# octanis_eps_v06.net
KiCad netlist of a schematic drawn in EAGLE
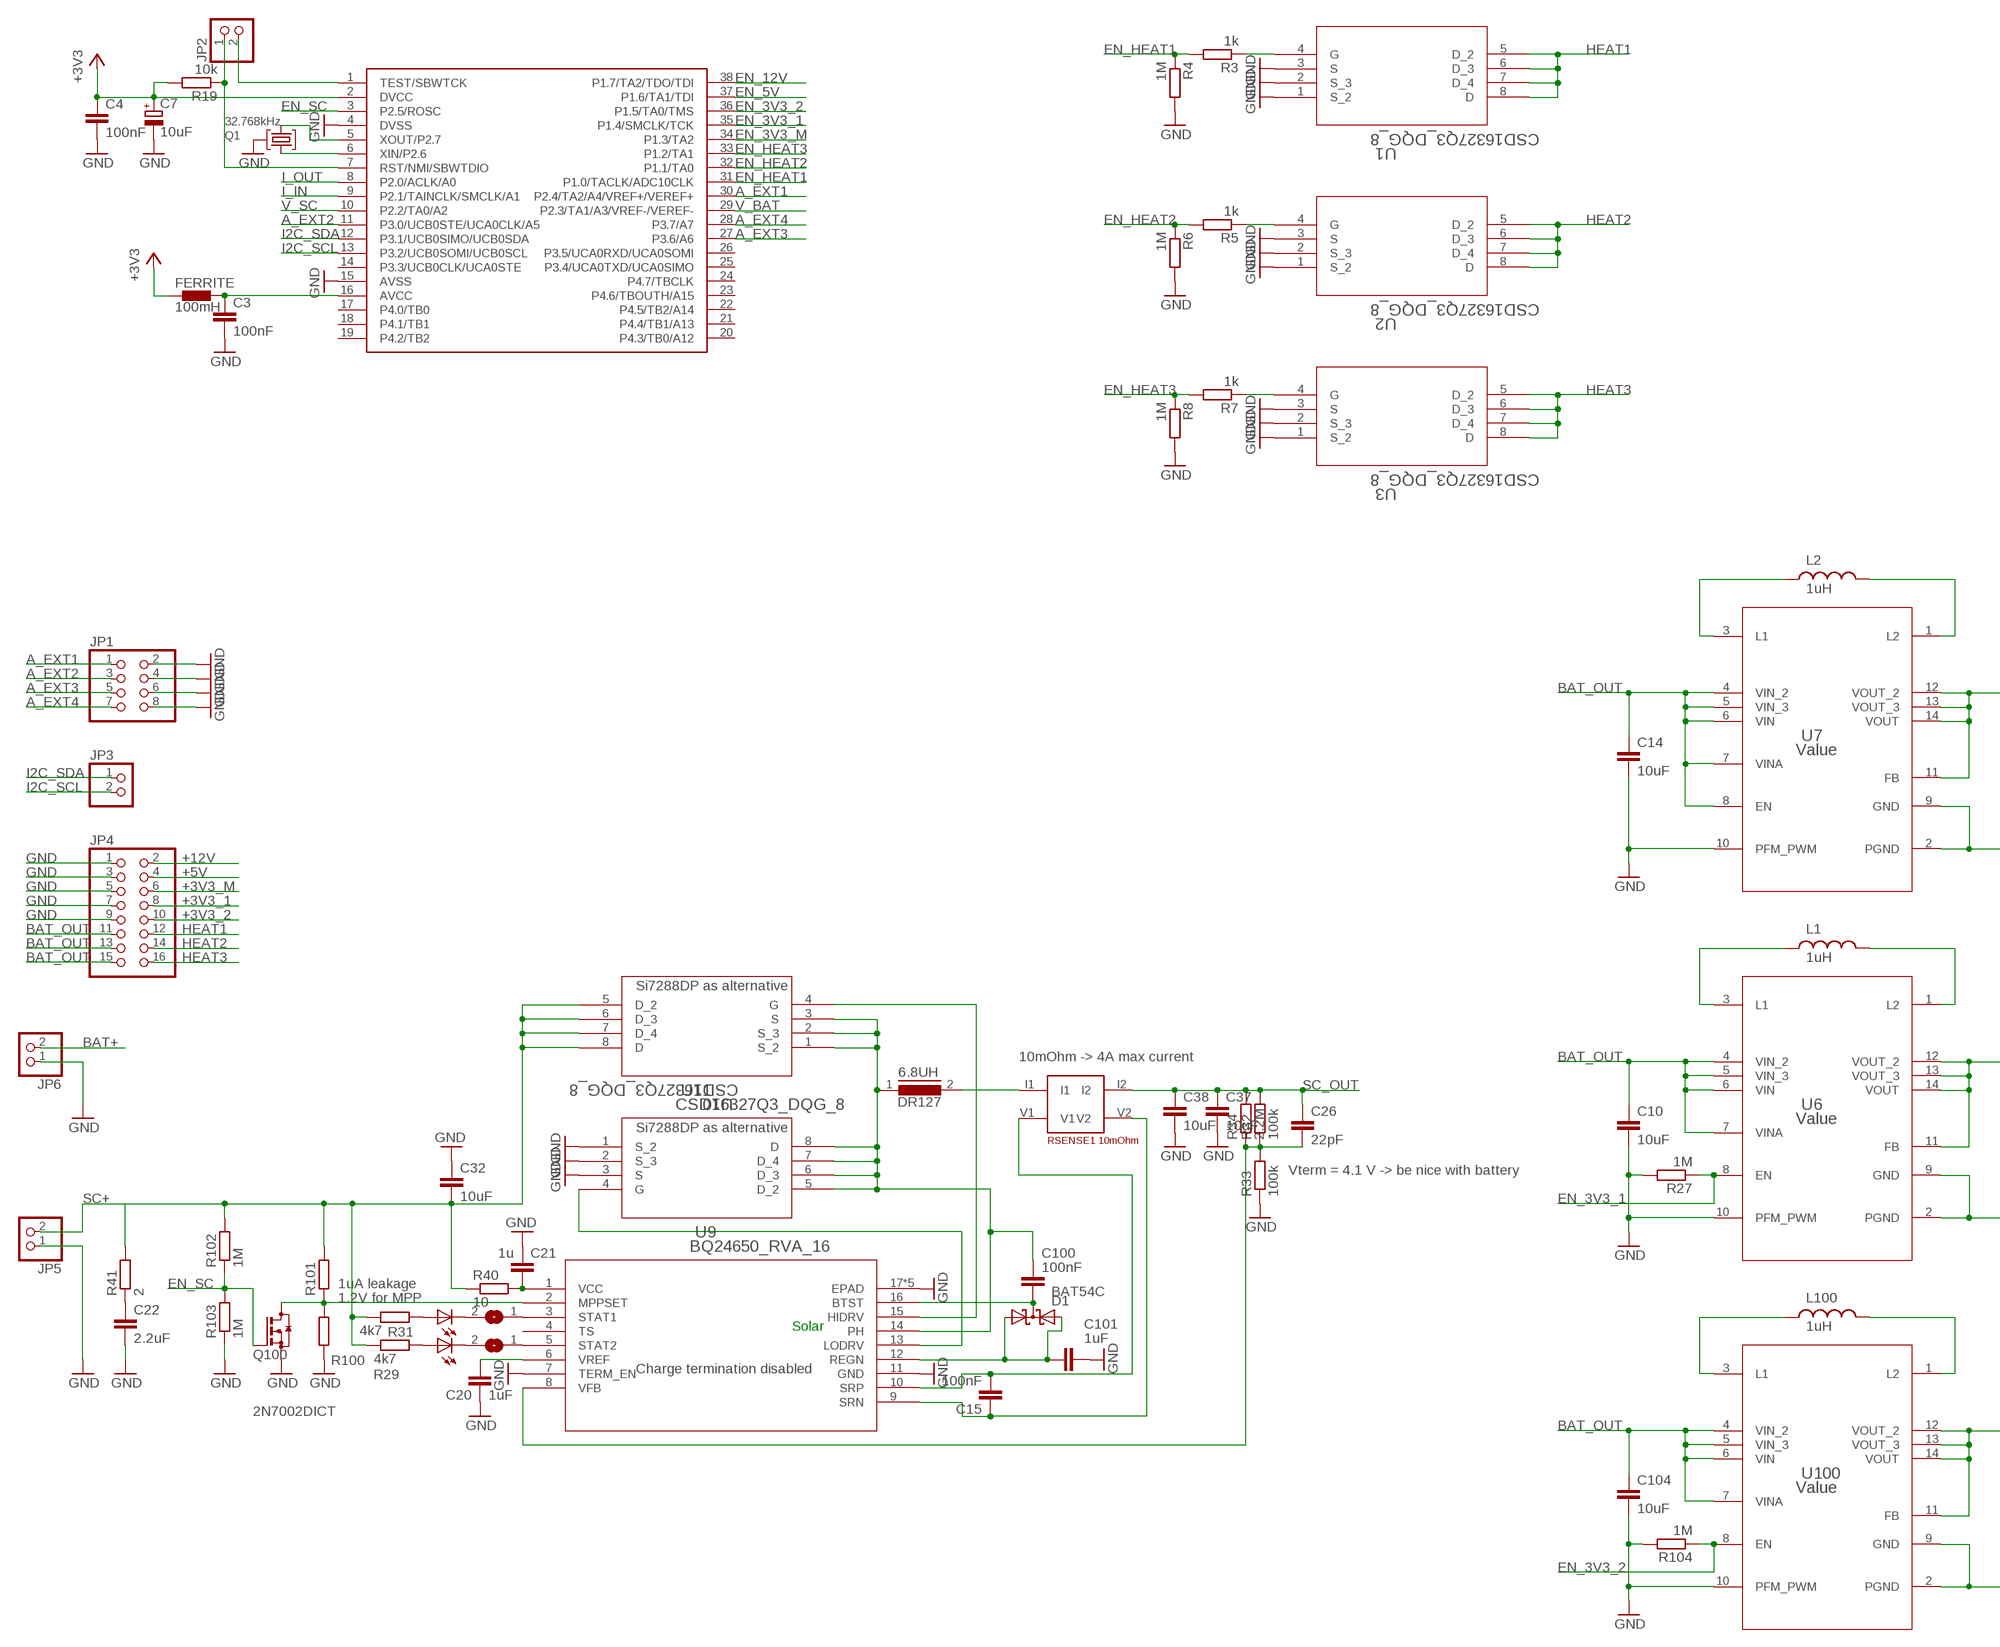
[diagram p0: schematic, sheet 1, part 1 of 2]
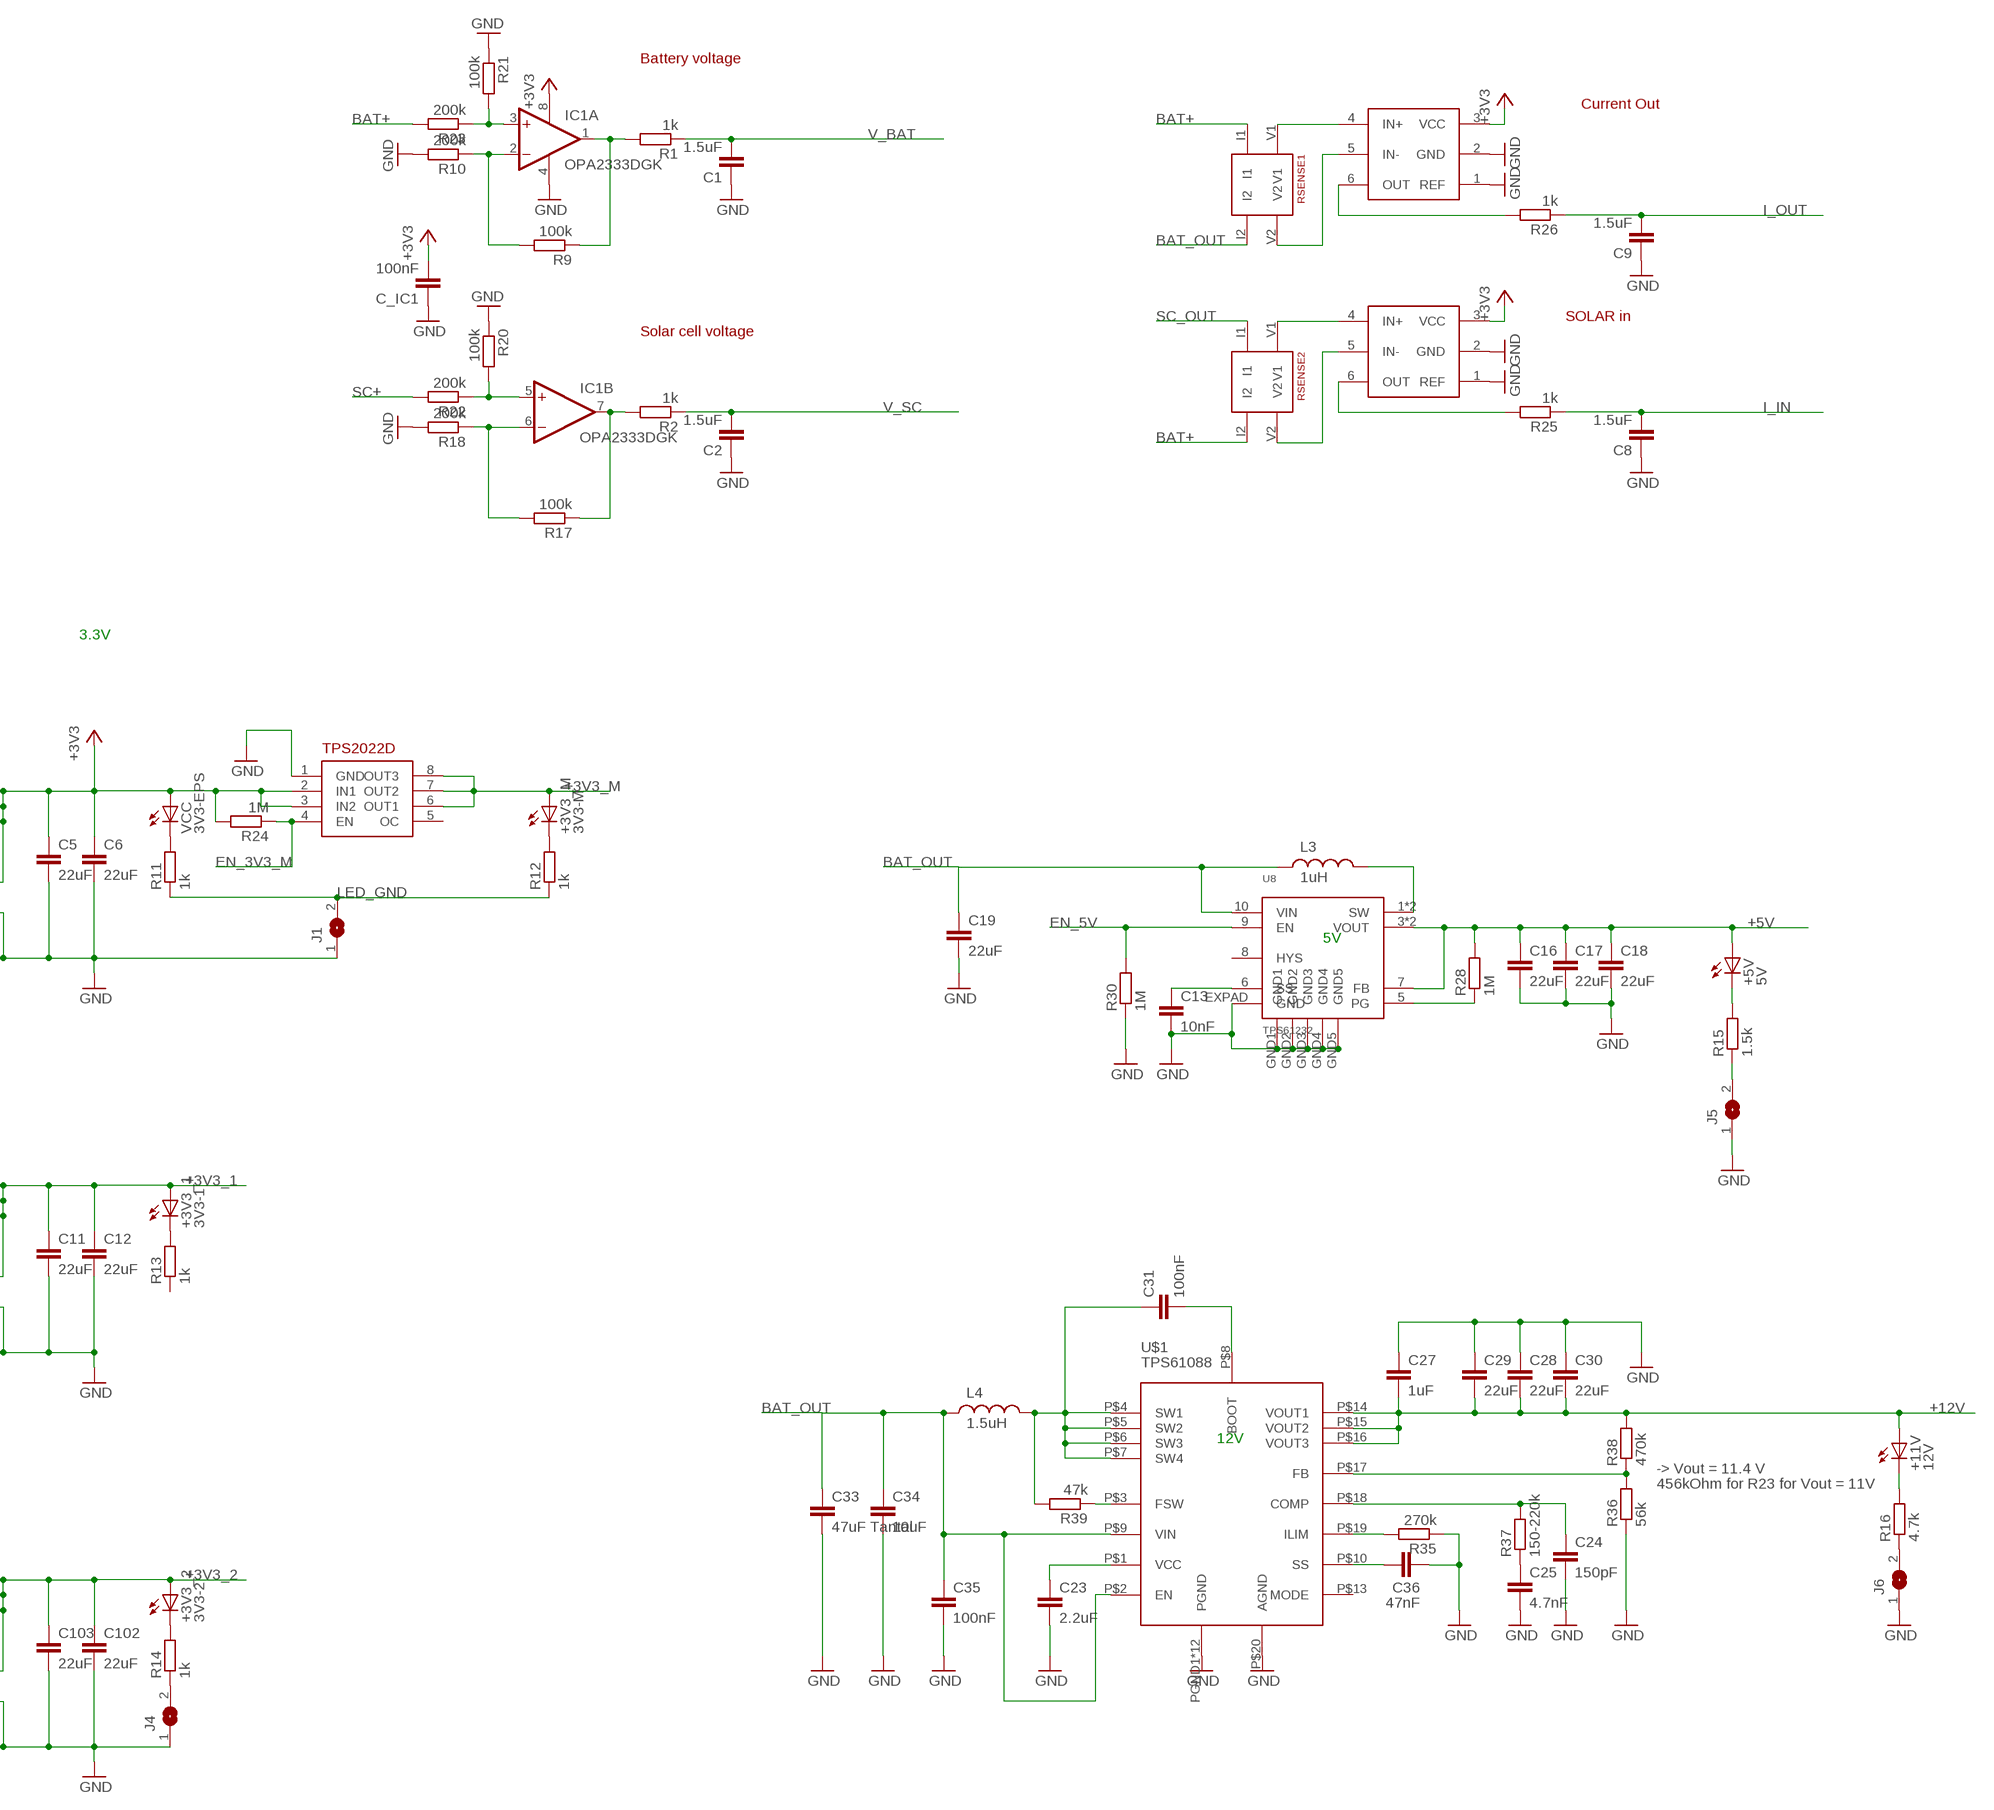
[diagram p1: schematic, sheet 1, part 2 of 2]

(export (version "E")
  (design (tool "Eeschema 10.0.6"))
  (components
    (comp (ref "+3V3_1")
      (value "3V3-1")
      (footprint "eagle-import:CHIPLED_0603")
      (libsource (lib "eagle-import") (part "LEDCHIPLED_0603"))
    )
    (comp (ref "+3V3_2")
      (value "3V3-2")
      (footprint "eagle-import:CHIPLED_0603")
      (libsource (lib "eagle-import") (part "LEDCHIPLED_0603"))
    )
    (comp (ref "+3V3_M")
      (value "3V3-M")
      (footprint "eagle-import:CHIPLED_0603")
      (libsource (lib "eagle-import") (part "LEDCHIPLED_0603"))
    )
    (comp (ref "+5V")
      (value "5V")
      (footprint "eagle-import:CHIPLED_0603")
      (libsource (lib "eagle-import") (part "LEDCHIPLED_0603"))
    )
    (comp (ref "+11V")
      (value "12V")
      (footprint "eagle-import:CHIPLED_0603")
      (libsource (lib "eagle-import") (part "LEDCHIPLED_0603"))
    )
    (comp (ref "6.8UH")
      (value "DR127")
      (footprint "eagle-import:DR127")
      (libsource (lib "eagle-import") (part "DR127"))
    )
    (comp (ref "C1")
      (value "1.5uF")
      (footprint "eagle-import:C0603")
      (libsource (lib "eagle-import") (part "C-EUC0603"))
    )
    (comp (ref "C2")
      (value "1.5uF")
      (footprint "eagle-import:C0603")
      (libsource (lib "eagle-import") (part "C-EUC0603"))
    )
    (comp (ref "C3")
      (value "100nF")
      (footprint "eagle-import:C0603")
      (libsource (lib "eagle-import") (part "C-EUC0603"))
    )
    (comp (ref "C4")
      (value "100nF")
      (footprint "eagle-import:C0603")
      (libsource (lib "eagle-import") (part "C-EUC0603"))
    )
    (comp (ref "C5")
      (value "22uF")
      (footprint "eagle-import:C0805")
      (libsource (lib "eagle-import") (part "resistor_C-EUC0805"))
    )
    (comp (ref "C6")
      (value "22uF")
      (footprint "eagle-import:C0805")
      (libsource (lib "eagle-import") (part "resistor_C-EUC0805"))
    )
    (comp (ref "C7")
      (value "10uF")
      (footprint "eagle-import:A_3216-18R")
      (libsource (lib "eagle-import") (part "CPOL-EUA/3216-18R"))
    )
    (comp (ref "C8")
      (value "1.5uF")
      (footprint "eagle-import:C0603")
      (libsource (lib "eagle-import") (part "C-EUC0603"))
    )
    (comp (ref "C9")
      (value "1.5uF")
      (footprint "eagle-import:C0603")
      (libsource (lib "eagle-import") (part "C-EUC0603"))
    )
    (comp (ref "C10")
      (value "10uF")
      (footprint "eagle-import:C0805")
      (libsource (lib "eagle-import") (part "resistor_C-EUC0805"))
    )
    (comp (ref "C11")
      (value "22uF")
      (footprint "eagle-import:C0805")
      (libsource (lib "eagle-import") (part "resistor_C-EUC0805"))
    )
    (comp (ref "C12")
      (value "22uF")
      (footprint "eagle-import:C0805")
      (libsource (lib "eagle-import") (part "resistor_C-EUC0805"))
    )
    (comp (ref "C13")
      (value "10nF")
      (footprint "eagle-import:C0603")
      (libsource (lib "eagle-import") (part "C-EUC0603"))
    )
    (comp (ref "C14")
      (value "10uF")
      (footprint "eagle-import:C0805")
      (libsource (lib "eagle-import") (part "resistor_C-EUC0805"))
    )
    (comp (ref "C15")
      (value "100nF")
      (footprint "eagle-import:C0603")
      (libsource (lib "eagle-import") (part "C-EUC0603"))
    )
    (comp (ref "C16")
      (value "22uF")
      (footprint "eagle-import:C0805")
      (libsource (lib "eagle-import") (part "resistor_C-EUC0805"))
    )
    (comp (ref "C17")
      (value "22uF")
      (footprint "eagle-import:C0805")
      (libsource (lib "eagle-import") (part "resistor_C-EUC0805"))
    )
    (comp (ref "C18")
      (value "22uF")
      (footprint "eagle-import:C0805")
      (libsource (lib "eagle-import") (part "resistor_C-EUC0805"))
    )
    (comp (ref "C19")
      (value "22uF")
      (footprint "eagle-import:C0603")
      (libsource (lib "eagle-import") (part "C-EUC0603"))
    )
    (comp (ref "C20")
      (value "1uF")
      (footprint "eagle-import:C0603")
      (libsource (lib "eagle-import") (part "C-EUC0603"))
    )
    (comp (ref "C21")
      (value "1u")
      (footprint "eagle-import:C0603")
      (libsource (lib "eagle-import") (part "C-EUC0603"))
    )
    (comp (ref "C22")
      (value "2.2uF")
      (footprint "eagle-import:C0603")
      (libsource (lib "eagle-import") (part "C-EUC0603"))
    )
    (comp (ref "C23")
      (value "2.2uF")
      (footprint "eagle-import:C0603")
      (libsource (lib "eagle-import") (part "C-EUC0603"))
    )
    (comp (ref "C24")
      (value "150pF")
      (footprint "eagle-import:C0603")
      (libsource (lib "eagle-import") (part "C-EUC0603"))
    )
    (comp (ref "C25")
      (value "4.7nF")
      (footprint "eagle-import:C0603")
      (libsource (lib "eagle-import") (part "C-EUC0603"))
    )
    (comp (ref "C26")
      (value "22pF")
      (footprint "eagle-import:C0603")
      (libsource (lib "eagle-import") (part "C-EUC0603"))
    )
    (comp (ref "C27")
      (value "1uF")
      (footprint "eagle-import:C0603")
      (libsource (lib "eagle-import") (part "C-EUC0603"))
    )
    (comp (ref "C28")
      (value "22uF")
      (footprint "eagle-import:C0805")
      (libsource (lib "eagle-import") (part "resistor_C-EUC0805"))
    )
    (comp (ref "C29")
      (value "22uF")
      (footprint "eagle-import:C0805")
      (libsource (lib "eagle-import") (part "resistor_C-EUC0805"))
    )
    (comp (ref "C30")
      (value "22uF")
      (footprint "eagle-import:C0805")
      (libsource (lib "eagle-import") (part "resistor_C-EUC0805"))
    )
    (comp (ref "C31")
      (value "100nF")
      (footprint "eagle-import:C0603")
      (libsource (lib "eagle-import") (part "C-EUC0603"))
    )
    (comp (ref "C32")
      (value "10uF")
      (footprint "eagle-import:C0805")
      (libsource (lib "eagle-import") (part "resistor_C-EUC0805"))
    )
    (comp (ref "C33")
      (value "47uF Tantal")
      (footprint "eagle-import:C1210")
      (libsource (lib "eagle-import") (part "C-EUC1210"))
    )
    (comp (ref "C34")
      (value "10uF")
      (footprint "eagle-import:C0805")
      (libsource (lib "eagle-import") (part "resistor_C-EUC0805"))
    )
    (comp (ref "C35")
      (value "100nF")
      (footprint "eagle-import:C0603")
      (libsource (lib "eagle-import") (part "C-EUC0603"))
    )
    (comp (ref "C36")
      (value "47nF")
      (footprint "eagle-import:C0603")
      (libsource (lib "eagle-import") (part "C-EUC0603"))
    )
    (comp (ref "C37")
      (value "10uF")
      (footprint "eagle-import:C0805")
      (libsource (lib "eagle-import") (part "resistor_C-EUC0805"))
    )
    (comp (ref "C38")
      (value "10uF")
      (footprint "eagle-import:C0805")
      (libsource (lib "eagle-import") (part "resistor_C-EUC0805"))
    )
    (comp (ref "C100")
      (value "100nF")
      (footprint "eagle-import:C0603")
      (libsource (lib "eagle-import") (part "C-EUC0603"))
    )
    (comp (ref "C101")
      (value "1uF")
      (footprint "eagle-import:C0603")
      (libsource (lib "eagle-import") (part "C-EUC0603"))
    )
    (comp (ref "C102")
      (value "22uF")
      (footprint "eagle-import:C0805")
      (libsource (lib "eagle-import") (part "resistor_C-EUC0805"))
    )
    (comp (ref "C103")
      (value "22uF")
      (footprint "eagle-import:C0805")
      (libsource (lib "eagle-import") (part "resistor_C-EUC0805"))
    )
    (comp (ref "C104")
      (value "10uF")
      (footprint "eagle-import:C0805")
      (libsource (lib "eagle-import") (part "resistor_C-EUC0805"))
    )
    (comp (ref "C_IC1")
      (value "100nF")
      (footprint "eagle-import:C0603")
      (libsource (lib "eagle-import") (part "C-EUC0603"))
    )
    (comp (ref "D1")
      (value "BAT54C")
      (footprint "eagle-import:SOT23")
      (libsource (lib "eagle-import") (part "BAT54C"))
    )
    (comp (ref "FERRITE")
      (value "100mH")
      (footprint "eagle-import:0402")
      (libsource (lib "eagle-import") (part "BLM15HD601SN1"))
    )
    (comp (ref "IC1")
      (value "OPA2333DGK")
      (footprint "eagle-import:MSOP08")
      (libsource (lib "eagle-import") (part "OPA2333DGK"))
    )
    (comp (ref "J1") (value "SJ") (footprint "eagle-import:SJ") (libsource (lib "eagle-import") (part "SJ")))
    (comp (ref "J4") (value "SJ") (footprint "eagle-import:SJ") (libsource (lib "eagle-import") (part "SJ")))
    (comp (ref "J5") (value "SJ") (footprint "eagle-import:SJ") (libsource (lib "eagle-import") (part "SJ")))
    (comp (ref "J6") (value "SJ") (footprint "eagle-import:SJ") (libsource (lib "eagle-import") (part "SJ")))
    (comp (ref "J7") (value "SJ") (footprint "eagle-import:SJ") (libsource (lib "eagle-import") (part "SJ")))
    (comp (ref "J8") (value "SJ") (footprint "eagle-import:SJ") (libsource (lib "eagle-import") (part "SJ")))
    (comp (ref "JP1")
      (value "PINHD-2X4")
      (footprint "eagle-import:2X04")
      (libsource (lib "eagle-import") (part "PINHD-2X4"))
    )
    (comp (ref "JP2")
      (value "PINHD-1X2")
      (footprint "eagle-import:1X02")
      (libsource (lib "eagle-import") (part "PINHD-1X2"))
    )
    (comp (ref "JP3")
      (value "PINHD-1X2")
      (footprint "eagle-import:1X02")
      (libsource (lib "eagle-import") (part "PINHD-1X2"))
    )
    (comp (ref "JP4")
      (value "PINHD-2X8")
      (footprint "eagle-import:2X08")
      (libsource (lib "eagle-import") (part "PINHD-2X8"))
    )
    (comp (ref "JP5")
      (value "PINHD-1X2")
      (footprint "eagle-import:1X02")
      (libsource (lib "eagle-import") (part "PINHD-1X2"))
    )
    (comp (ref "JP6")
      (value "PINHD-1X2")
      (footprint "eagle-import:1X02")
      (libsource (lib "eagle-import") (part "PINHD-1X2"))
    )
    (comp (ref "L1")
      (value "1uH")
      (footprint "eagle-import:XFL4020")
      (libsource (lib "eagle-import") (part "XFL4020"))
    )
    (comp (ref "L2")
      (value "1uH")
      (footprint "eagle-import:XFL4020")
      (libsource (lib "eagle-import") (part "XFL4020"))
    )
    (comp (ref "L3")
      (value "1uH")
      (footprint "eagle-import:XFL4020")
      (libsource (lib "eagle-import") (part "XFL4020"))
    )
    (comp (ref "L4")
      (value "1.5uH")
      (footprint "eagle-import:XFL4020")
      (libsource (lib "eagle-import") (part "XFL4020"))
    )
    (comp (ref "L100")
      (value "1uH")
      (footprint "eagle-import:XFL4020")
      (libsource (lib "eagle-import") (part "XFL4020"))
    )
    (comp (ref "Q1")
      (value "32.768kHz")
      (footprint "eagle-import:MS3V-T1R")
      (libsource (lib "eagle-import") (part "MS3V-T1R"))
    )
    (comp (ref "Q100")
      (value "BSS123")
      (footprint "eagle-import:SOT23")
      (libsource (lib "eagle-import") (part "BSS123"))
    )
    (comp (ref "R1")
      (value "1k")
      (footprint "eagle-import:R0603")
      (libsource (lib "eagle-import") (part "R-EU_R0603"))
    )
    (comp (ref "R2")
      (value "1k")
      (footprint "eagle-import:R0603")
      (libsource (lib "eagle-import") (part "R-EU_R0603"))
    )
    (comp (ref "R3")
      (value "1k")
      (footprint "eagle-import:R0603")
      (libsource (lib "eagle-import") (part "R-EU_R0603"))
    )
    (comp (ref "R4")
      (value "1M")
      (footprint "eagle-import:R0603")
      (libsource (lib "eagle-import") (part "R-EU_R0603"))
    )
    (comp (ref "R5")
      (value "1k")
      (footprint "eagle-import:R0603")
      (libsource (lib "eagle-import") (part "R-EU_R0603"))
    )
    (comp (ref "R6")
      (value "1M")
      (footprint "eagle-import:R0603")
      (libsource (lib "eagle-import") (part "R-EU_R0603"))
    )
    (comp (ref "R7")
      (value "1k")
      (footprint "eagle-import:R0603")
      (libsource (lib "eagle-import") (part "R-EU_R0603"))
    )
    (comp (ref "R8")
      (value "1M")
      (footprint "eagle-import:R0603")
      (libsource (lib "eagle-import") (part "R-EU_R0603"))
    )
    (comp (ref "R9")
      (value "100k")
      (footprint "eagle-import:R0603")
      (libsource (lib "eagle-import") (part "R-EU_R0603"))
    )
    (comp (ref "R10")
      (value "200k")
      (footprint "eagle-import:R0603")
      (libsource (lib "eagle-import") (part "R-EU_R0603"))
    )
    (comp (ref "R11")
      (value "1k")
      (footprint "eagle-import:R0603")
      (libsource (lib "eagle-import") (part "R-EU_R0603"))
    )
    (comp (ref "R12")
      (value "1k")
      (footprint "eagle-import:R0603")
      (libsource (lib "eagle-import") (part "R-EU_R0603"))
    )
    (comp (ref "R13")
      (value "1k")
      (footprint "eagle-import:R0603")
      (libsource (lib "eagle-import") (part "R-EU_R0603"))
    )
    (comp (ref "R14")
      (value "1k")
      (footprint "eagle-import:R0603")
      (libsource (lib "eagle-import") (part "R-EU_R0603"))
    )
    (comp (ref "R15")
      (value "1.5k")
      (footprint "eagle-import:R0603")
      (libsource (lib "eagle-import") (part "R-EU_R0603"))
    )
    (comp (ref "R16")
      (value "4.7k")
      (footprint "eagle-import:R0603")
      (libsource (lib "eagle-import") (part "R-EU_R0603"))
    )
    (comp (ref "R17")
      (value "100k")
      (footprint "eagle-import:R0603")
      (libsource (lib "eagle-import") (part "R-EU_R0603"))
    )
    (comp (ref "R18")
      (value "200k")
      (footprint "eagle-import:R0603")
      (libsource (lib "eagle-import") (part "R-EU_R0603"))
    )
    (comp (ref "R19")
      (value "10k")
      (footprint "eagle-import:R0603")
      (libsource (lib "eagle-import") (part "R-EU_R0603"))
    )
    (comp (ref "R20")
      (value "100k")
      (footprint "eagle-import:R0603")
      (libsource (lib "eagle-import") (part "R-EU_R0603"))
    )
    (comp (ref "R21")
      (value "100k")
      (footprint "eagle-import:R0603")
      (libsource (lib "eagle-import") (part "R-EU_R0603"))
    )
    (comp (ref "R22")
      (value "200k")
      (footprint "eagle-import:R0603")
      (libsource (lib "eagle-import") (part "R-EU_R0603"))
    )
    (comp (ref "R23")
      (value "200k")
      (footprint "eagle-import:R0603")
      (libsource (lib "eagle-import") (part "R-EU_R0603"))
    )
    (comp (ref "R24")
      (value "1M")
      (footprint "eagle-import:R0603")
      (libsource (lib "eagle-import") (part "resistor_R-EU_R0603"))
    )
    (comp (ref "R25")
      (value "1k")
      (footprint "eagle-import:R0603")
      (libsource (lib "eagle-import") (part "R-EU_R0603"))
    )
    (comp (ref "R26")
      (value "1k")
      (footprint "eagle-import:R0603")
      (libsource (lib "eagle-import") (part "R-EU_R0603"))
    )
    (comp (ref "R27")
      (value "1M")
      (footprint "eagle-import:R0603")
      (libsource (lib "eagle-import") (part "resistor_R-EU_R0603"))
    )
    (comp (ref "R28")
      (value "1M")
      (footprint "eagle-import:R0603")
      (libsource (lib "eagle-import") (part "R-EU_R0603"))
    )
    (comp (ref "R29")
      (value "4k7")
      (footprint "eagle-import:R0603")
      (libsource (lib "eagle-import") (part "R-EU_R0603"))
    )
    (comp (ref "R30")
      (value "1M")
      (footprint "eagle-import:R0603")
      (libsource (lib "eagle-import") (part "R-EU_R0603"))
    )
    (comp (ref "R31")
      (value "4k7")
      (footprint "eagle-import:R0603")
      (libsource (lib "eagle-import") (part "R-EU_R0603"))
    )
    (comp (ref "R32")
      (value "100k")
      (footprint "eagle-import:R0603")
      (libsource (lib "eagle-import") (part "R-EU_R0603"))
    )
    (comp (ref "R33")
      (value "100k")
      (footprint "eagle-import:R0603")
      (libsource (lib "eagle-import") (part "R-EU_R0603"))
    )
    (comp (ref "R34")
      (value "2.2M")
      (footprint "eagle-import:R0603")
      (libsource (lib "eagle-import") (part "R-EU_R0603"))
    )
    (comp (ref "R35")
      (value "270k")
      (footprint "eagle-import:R0603")
      (libsource (lib "eagle-import") (part "resistor_R-EU_R0603"))
    )
    (comp (ref "R36")
      (value "56k")
      (footprint "eagle-import:R0603")
      (libsource (lib "eagle-import") (part "resistor_R-EU_R0603"))
    )
    (comp (ref "R37")
      (value "150-220k")
      (footprint "eagle-import:R0603")
      (libsource (lib "eagle-import") (part "resistor_R-EU_R0603"))
    )
    (comp (ref "R38")
      (value "470k")
      (footprint "eagle-import:R0603")
      (libsource (lib "eagle-import") (part "resistor_R-EU_R0603"))
    )
    (comp (ref "R39")
      (value "47k")
      (footprint "eagle-import:R0603")
      (libsource (lib "eagle-import") (part "resistor_R-EU_R0603"))
    )
    (comp (ref "R40")
      (value "10")
      (footprint "eagle-import:R1206")
      (libsource (lib "eagle-import") (part "R-EU_R1206"))
    )
    (comp (ref "R41")
      (value "2")
      (footprint "eagle-import:R2012")
      (libsource (lib "eagle-import") (part "R-EU_R2012"))
    )
    (comp (ref "R100")
      (value "R-EU_R0603")
      (footprint "eagle-import:R0603")
      (libsource (lib "eagle-import") (part "R-EU_R0603"))
    )
    (comp (ref "R101")
      (value "R-EU_R0603")
      (footprint "eagle-import:R0603")
      (libsource (lib "eagle-import") (part "R-EU_R0603"))
    )
    (comp (ref "R102")
      (value "1M")
      (footprint "eagle-import:R0603")
      (libsource (lib "eagle-import") (part "R-EU_R0603"))
    )
    (comp (ref "R103")
      (value "1M")
      (footprint "eagle-import:R0603")
      (libsource (lib "eagle-import") (part "R-EU_R0603"))
    )
    (comp (ref "R104")
      (value "1M")
      (footprint "eagle-import:R0603")
      (libsource (lib "eagle-import") (part "resistor_R-EU_R0603"))
    )
    (comp (ref "RSENSE1")
      (value "RSENSE2")
      (footprint "eagle-import:4PADS_RESISTOR")
      (libsource (lib "eagle-import") (part "CURRENT_RESISTOR"))
    )
    (comp (ref "R_SENSE1")
      (value "RSENSE1 10mOhm")
      (footprint "eagle-import:4PADS_RESISTOR")
      (libsource (lib "eagle-import") (part "CURRENT_RESISTOR"))
    )
    (comp (ref "R_SENSE2")
      (value "RSENSE1")
      (footprint "eagle-import:4PADS_RESISTOR")
      (libsource (lib "eagle-import") (part "CURRENT_RESISTOR"))
    )
    (comp (ref "STAT1")
      (value "5V-ok")
      (footprint "eagle-import:CHIPLED_0603")
      (libsource (lib "eagle-import") (part "LEDCHIPLED_0603"))
    )
    (comp (ref "STAT2")
      (value "5V-ok")
      (footprint "eagle-import:CHIPLED_0603")
      (libsource (lib "eagle-import") (part "LEDCHIPLED_0603"))
    )
    (comp (ref "U$1")
      (value "TPS61088")
      (footprint "eagle-import:R-PVQFN-N20")
      (libsource (lib "eagle-import") (part "TPS61088"))
    )
    (comp (ref "U$2")
      (value "INA213")
      (footprint "eagle-import:SC70-6")
      (libsource (lib "eagle-import") (part "INA213"))
    )
    (comp (ref "U$3")
      (value "INA213")
      (footprint "eagle-import:SC70-6")
      (libsource (lib "eagle-import") (part "INA213"))
    )
    (comp (ref "U1")
      (value "CSD16327Q3_DQG_8")
      (footprint "eagle-import:DQG8")
      (fields
        (field (name "GENERIC_PART_NUMBER") "CSD16327Q3")
        (field (name "MANUFACTURER") "Texas Instruments")
      )
      (libsource (lib "eagle-import") (part "CSD16327Q3_DQG_8"))
    )
    (comp (ref "U2")
      (value "CSD16327Q3_DQG_8")
      (footprint "eagle-import:DQG8")
      (fields
        (field (name "GENERIC_PART_NUMBER") "CSD16327Q3")
        (field (name "MANUFACTURER") "Texas Instruments")
      )
      (libsource (lib "eagle-import") (part "CSD16327Q3_DQG_8"))
    )
    (comp (ref "U3")
      (value "CSD16327Q3_DQG_8")
      (footprint "eagle-import:DQG8")
      (fields
        (field (name "GENERIC_PART_NUMBER") "CSD16327Q3")
        (field (name "MANUFACTURER") "Texas Instruments")
      )
      (libsource (lib "eagle-import") (part "CSD16327Q3_DQG_8"))
    )
    (comp (ref "U4")
      (value "MSP430G2544")
      (footprint "eagle-import:TSSOP38_MSPGXX44_SERIES")
      (libsource (lib "eagle-import") (part "MSP430G2544"))
    )
    (comp (ref "U5")
      (value "TPS2022D")
      (footprint "eagle-import:SO8")
      (libsource (lib "eagle-import") (part "TPS2022D"))
    )
    (comp (ref "U6")
      (value "Value")
      (footprint "eagle-import:RNC0014A")
      (fields
        (field (name "ALTERNATEPARTNUMBER") "TPS630250RNCT")
        (field (name "MANUFACTURER") "Texas Instruments")
        (field (name "PARTNUMBER") "TPS630250RNCR")
      )
      (libsource (lib "eagle-import") (part "TPS630250RNCR"))
    )
    (comp (ref "U7")
      (value "Value")
      (footprint "eagle-import:RNC0014A")
      (fields
        (field (name "ALTERNATEPARTNUMBER") "TPS630250RNCT")
        (field (name "MANUFACTURER") "Texas Instruments")
        (field (name "PARTNUMBER") "TPS630250RNCR")
      )
      (libsource (lib "eagle-import") (part "TPS630250RNCR"))
    )
    (comp (ref "U8")
      (value "TPS61232")
      (footprint "eagle-import:S-PVSON-N10")
      (libsource (lib "eagle-import") (part "TPS61232"))
    )
    (comp (ref "U9")
      (value "BQ24650_RVA_16")
      (footprint "eagle-import:RVA16_2P14X2P14")
      (fields
        (field (name "GENERIC_PART_NUMBER") "BQ24650")
        (field (name "MANUFACTURER") "Texas Instruments")
      )
      (libsource (lib "eagle-import") (part "BQ24650_RVA_16"))
    )
    (comp (ref "U10")
      (value "CSD16327Q3_DQG_8")
      (footprint "eagle-import:DQG8")
      (fields
        (field (name "GENERIC_PART_NUMBER") "CSD16327Q3")
        (field (name "MANUFACTURER") "Texas Instruments")
      )
      (libsource (lib "eagle-import") (part "CSD16327Q3_DQG_8"))
    )
    (comp (ref "U11")
      (value "CSD16327Q3_DQG_8")
      (footprint "eagle-import:DQG8")
      (fields
        (field (name "GENERIC_PART_NUMBER") "CSD16327Q3")
        (field (name "MANUFACTURER") "Texas Instruments")
      )
      (libsource (lib "eagle-import") (part "CSD16327Q3_DQG_8"))
    )
    (comp (ref "U100")
      (value "Value")
      (footprint "eagle-import:RNC0014A")
      (fields
        (field (name "ALTERNATEPARTNUMBER") "TPS630250RNCT")
        (field (name "MANUFACTURER") "Texas Instruments")
        (field (name "PARTNUMBER") "TPS630250RNCR")
      )
      (libsource (lib "eagle-import") (part "TPS630250RNCR"))
    )
    (comp (ref "VCC")
      (value "3V3-EPS")
      (footprint "eagle-import:CHIPLED_0603")
      (libsource (lib "eagle-import") (part "LEDCHIPLED_0603"))
    )
  )
  (nets
    (net (code "1") (name "+3V3") (class "Default")
      (node (ref "C4") (pin "1") (pinfunction "1_1") (pintype "passive"))
      (node (ref "C5") (pin "1") (pinfunction "1_1") (pintype "passive"))
      (node (ref "C6") (pin "1") (pinfunction "1_1") (pintype "passive"))
      (node (ref "C7") (pin "+") (pinfunction "+_+") (pintype "passive"))
      (node (ref "C_IC1") (pin "2") (pinfunction "2_2") (pintype "passive"))
      (node (ref "FERRITE") (pin "1") (pinfunction "1_1") (pintype "passive"))
      (node (ref "IC1") (pin "8") (pinfunction "V+_8") (pintype "power_in"))
      (node (ref "R19") (pin "2") (pinfunction "2_2") (pintype "passive"))
      (node (ref "R24") (pin "2") (pinfunction "2_2") (pintype "passive"))
      (node (ref "U$2") (pin "3") (pinfunction "VCC_3") (pintype "bidirectional"))
      (node (ref "U$3") (pin "3") (pinfunction "VCC_3") (pintype "bidirectional"))
      (node (ref "U4") (pin "2") (pinfunction "DVCC_2") (pintype "bidirectional"))
      (node (ref "U5") (pin "2") (pinfunction "IN1_2") (pintype "bidirectional"))
      (node (ref "U5") (pin "3") (pinfunction "IN2_3") (pintype "bidirectional"))
      (node (ref "U7") (pin "11") (pinfunction "FB_11") (pintype "input"))
      (node (ref "U7") (pin "12") (pinfunction "VOUT_2_12") (pintype "power_in"))
      (node (ref "U7") (pin "13") (pinfunction "VOUT_3_13") (pintype "power_in"))
      (node (ref "U7") (pin "14") (pinfunction "VOUT_14") (pintype "power_in"))
      (node (ref "VCC") (pin "A") (pinfunction "A_A") (pintype "passive"))
    )
    (net (code "2") (name "/+3V3_1") (class "Default")
      (node (ref "+3V3_1") (pin "A") (pinfunction "A_A") (pintype "passive"))
      (node (ref "C11") (pin "1") (pinfunction "1_1") (pintype "passive"))
      (node (ref "C12") (pin "1") (pinfunction "1_1") (pintype "passive"))
      (node (ref "JP4") (pin "8") (pinfunction "8_8") (pintype "passive"))
      (node (ref "U6") (pin "11") (pinfunction "FB_11") (pintype "input"))
      (node (ref "U6") (pin "12") (pinfunction "VOUT_2_12") (pintype "power_in"))
      (node (ref "U6") (pin "13") (pinfunction "VOUT_3_13") (pintype "power_in"))
      (node (ref "U6") (pin "14") (pinfunction "VOUT_14") (pintype "power_in"))
    )
    (net (code "3") (name "/+3V3_2") (class "Default")
      (node (ref "+3V3_2") (pin "A") (pinfunction "A_A") (pintype "passive"))
      (node (ref "C102") (pin "1") (pinfunction "1_1") (pintype "passive"))
      (node (ref "C103") (pin "1") (pinfunction "1_1") (pintype "passive"))
      (node (ref "JP4") (pin "10") (pinfunction "10_10") (pintype "passive"))
      (node (ref "U100") (pin "11") (pinfunction "FB_11") (pintype "input"))
      (node (ref "U100") (pin "12") (pinfunction "VOUT_2_12") (pintype "power_in"))
      (node (ref "U100") (pin "13") (pinfunction "VOUT_3_13") (pintype "power_in"))
      (node (ref "U100") (pin "14") (pinfunction "VOUT_14") (pintype "power_in"))
    )
    (net (code "4") (name "/+3V3_M") (class "Default")
      (node (ref "+3V3_M") (pin "A") (pinfunction "A_A") (pintype "passive"))
      (node (ref "JP4") (pin "6") (pinfunction "6_6") (pintype "passive"))
      (node (ref "U5") (pin "6") (pinfunction "OUT1_6") (pintype "bidirectional"))
      (node (ref "U5") (pin "7") (pinfunction "OUT2_7") (pintype "bidirectional"))
      (node (ref "U5") (pin "8") (pinfunction "OUT3_8") (pintype "bidirectional"))
    )
    (net (code "5") (name "/+5V") (class "Default")
      (node (ref "+5V") (pin "A") (pinfunction "A_A") (pintype "passive"))
      (node (ref "C16") (pin "1") (pinfunction "1_1") (pintype "passive"))
      (node (ref "C17") (pin "1") (pinfunction "1_1") (pintype "passive"))
      (node (ref "C18") (pin "1") (pinfunction "1_1") (pintype "passive"))
      (node (ref "JP4") (pin "4") (pinfunction "4_4") (pintype "passive"))
      (node (ref "R28") (pin "2") (pinfunction "2_2") (pintype "passive"))
      (node (ref "U8") (pin "3") (pinfunction "VOUT_3") (pintype "power_in"))
      (node (ref "U8") (pin "4") (pinfunction "VOUT_4") (pintype "power_in"))
      (node (ref "U8") (pin "7") (pinfunction "FB_7") (pintype "input"))
    )
    (net (code "6") (name "/+12V") (class "Default")
      (node (ref "+11V") (pin "A") (pinfunction "A_A") (pintype "passive"))
      (node (ref "C27") (pin "2") (pinfunction "2_2") (pintype "passive"))
      (node (ref "C28") (pin "2") (pinfunction "2_2") (pintype "passive"))
      (node (ref "C29") (pin "2") (pinfunction "2_2") (pintype "passive"))
      (node (ref "C30") (pin "2") (pinfunction "2_2") (pintype "passive"))
      (node (ref "JP4") (pin "2") (pinfunction "2_2") (pintype "passive"))
      (node (ref "R38") (pin "2") (pinfunction "2_2") (pintype "passive"))
      (node (ref "U$1") (pin "P$14") (pinfunction "VOUT1_P$14") (pintype "bidirectional"))
      (node (ref "U$1") (pin "P$15") (pinfunction "VOUT2_P$15") (pintype "bidirectional"))
      (node (ref "U$1") (pin "P$16") (pinfunction "VOUT3_P$16") (pintype "bidirectional"))
    )
    (net (code "7") (name "/A_EXT1") (class "Default")
      (node (ref "JP1") (pin "1") (pinfunction "1_1") (pintype "passive"))
      (node (ref "U4") (pin "30") (pinfunction "P2.4/TA2/A4/VREF+/VEREF+_30") (pintype "bidirectional"))
    )
    (net (code "8") (name "/A_EXT2") (class "Default")
      (node (ref "JP1") (pin "3") (pinfunction "3_3") (pintype "passive"))
      (node (ref "U4") (pin "11") (pinfunction "P3.0/UCB0STE/UCA0CLK/A5_11") (pintype "bidirectional"))
    )
    (net (code "9") (name "/A_EXT3") (class "Default")
      (node (ref "JP1") (pin "5") (pinfunction "5_5") (pintype "passive"))
      (node (ref "U4") (pin "27") (pinfunction "P3.6/A6_27") (pintype "bidirectional"))
    )
    (net (code "10") (name "/A_EXT4") (class "Default")
      (node (ref "JP1") (pin "7") (pinfunction "7_7") (pintype "passive"))
      (node (ref "U4") (pin "28") (pinfunction "P3.7/A7_28") (pintype "bidirectional"))
    )
    (net (code "11") (name "/BAT+") (class "Default")
      (node (ref "JP6") (pin "2") (pinfunction "2_2") (pintype "passive"))
      (node (ref "R23") (pin "2") (pinfunction "2_2") (pintype "passive"))
      (node (ref "RSENSE1") (pin "I2") (pinfunction "I2_I2") (pintype "bidirectional"))
      (node (ref "R_SENSE2") (pin "I1") (pinfunction "I1_I1") (pintype "bidirectional"))
    )
    (net (code "12") (name "/BAT_OUT") (class "Default")
      (node (ref "C10") (pin "1") (pinfunction "1_1") (pintype "passive"))
      (node (ref "C104") (pin "1") (pinfunction "1_1") (pintype "passive"))
      (node (ref "C14") (pin "1") (pinfunction "1_1") (pintype "passive"))
      (node (ref "C19") (pin "1") (pinfunction "1_1") (pintype "passive"))
      (node (ref "C33") (pin "1") (pinfunction "1_1") (pintype "passive"))
      (node (ref "C34") (pin "1") (pinfunction "1_1") (pintype "passive"))
      (node (ref "C35") (pin "1") (pinfunction "1_1") (pintype "passive"))
      (node (ref "JP4") (pin "11") (pinfunction "11_11") (pintype "passive"))
      (node (ref "JP4") (pin "13") (pinfunction "13_13") (pintype "passive"))
      (node (ref "JP4") (pin "15") (pinfunction "15_15") (pintype "passive"))
      (node (ref "L3") (pin "P$1") (pinfunction "1_P$1") (pintype "passive"))
      (node (ref "L4") (pin "P$1") (pinfunction "1_P$1") (pintype "passive"))
      (node (ref "R_SENSE2") (pin "I2") (pinfunction "I2_I2") (pintype "bidirectional"))
      (node (ref "U$1") (pin "P$2") (pinfunction "EN_P$2") (pintype "bidirectional"))
      (node (ref "U$1") (pin "P$9") (pinfunction "VIN_P$9") (pintype "bidirectional"))
      (node (ref "U100") (pin "4") (pinfunction "VIN_2_4") (pintype "power_in"))
      (node (ref "U100") (pin "5") (pinfunction "VIN_3_5") (pintype "power_in"))
      (node (ref "U100") (pin "6") (pinfunction "VIN_6") (pintype "power_in"))
      (node (ref "U100") (pin "7") (pinfunction "VINA_7") (pintype "power_in"))
      (node (ref "U6") (pin "4") (pinfunction "VIN_2_4") (pintype "power_in"))
      (node (ref "U6") (pin "5") (pinfunction "VIN_3_5") (pintype "power_in"))
      (node (ref "U6") (pin "6") (pinfunction "VIN_6") (pintype "power_in"))
      (node (ref "U6") (pin "7") (pinfunction "VINA_7") (pintype "power_in"))
      (node (ref "U7") (pin "4") (pinfunction "VIN_2_4") (pintype "power_in"))
      (node (ref "U7") (pin "5") (pinfunction "VIN_3_5") (pintype "power_in"))
      (node (ref "U7") (pin "6") (pinfunction "VIN_6") (pintype "power_in"))
      (node (ref "U7") (pin "7") (pinfunction "VINA_7") (pintype "power_in"))
      (node (ref "U7") (pin "8") (pinfunction "EN_8") (pintype "input"))
      (node (ref "U8") (pin "10") (pinfunction "VIN_10") (pintype "input"))
    )
    (net (code "13") (name "/EN_3V3_1") (class "Default")
      (node (ref "R27") (pin "1") (pinfunction "1_1") (pintype "passive"))
      (node (ref "U4") (pin "35") (pinfunction "P1.4/SMCLK/TCK_35") (pintype "bidirectional"))
      (node (ref "U6") (pin "8") (pinfunction "EN_8") (pintype "input"))
    )
    (net (code "14") (name "/EN_3V3_2") (class "Default")
      (node (ref "R104") (pin "1") (pinfunction "1_1") (pintype "passive"))
      (node (ref "U100") (pin "8") (pinfunction "EN_8") (pintype "input"))
      (node (ref "U4") (pin "36") (pinfunction "P1.5/TA0/TMS_36") (pintype "bidirectional"))
    )
    (net (code "15") (name "/EN_3V3_M") (class "Default")
      (node (ref "R24") (pin "1") (pinfunction "1_1") (pintype "passive"))
      (node (ref "U4") (pin "34") (pinfunction "P1.3/TA2_34") (pintype "bidirectional"))
      (node (ref "U5") (pin "4") (pinfunction "EN_4") (pintype "bidirectional"))
    )
    (net (code "16") (name "/EN_5V") (class "Default")
      (node (ref "R30") (pin "2") (pinfunction "2_2") (pintype "passive"))
      (node (ref "U4") (pin "37") (pinfunction "P1.6/TA1/TDI_37") (pintype "bidirectional"))
      (node (ref "U8") (pin "9") (pinfunction "EN_9") (pintype "input"))
    )
    (net (code "17") (name "/EN_12V") (class "Default")
      (node (ref "U4") (pin "38") (pinfunction "P1.7/TA2/TDO/TDI_38") (pintype "bidirectional"))
    )
    (net (code "18") (name "/EN_HEAT1") (class "Default")
      (node (ref "R3") (pin "2") (pinfunction "2_2") (pintype "passive"))
      (node (ref "R4") (pin "1") (pinfunction "1_1") (pintype "passive"))
      (node (ref "U4") (pin "31") (pinfunction "P1.0/TACLK/ADC10CLK_31") (pintype "bidirectional"))
    )
    (net (code "19") (name "/EN_HEAT2") (class "Default")
      (node (ref "R5") (pin "2") (pinfunction "2_2") (pintype "passive"))
      (node (ref "R6") (pin "1") (pinfunction "1_1") (pintype "passive"))
      (node (ref "U4") (pin "32") (pinfunction "P1.1/TA0_32") (pintype "bidirectional"))
    )
    (net (code "20") (name "/EN_HEAT3") (class "Default")
      (node (ref "R7") (pin "2") (pinfunction "2_2") (pintype "passive"))
      (node (ref "R8") (pin "1") (pinfunction "1_1") (pintype "passive"))
      (node (ref "U4") (pin "33") (pinfunction "P1.2/TA1_33") (pintype "bidirectional"))
    )
    (net (code "21") (name "/EN_SC") (class "Default")
      (node (ref "Q100") (pin "1") (pinfunction "G_1") (pintype "passive"))
      (node (ref "R102") (pin "1") (pinfunction "1_1") (pintype "passive"))
      (node (ref "R103") (pin "2") (pinfunction "2_2") (pintype "passive"))
      (node (ref "U4") (pin "3") (pinfunction "P2.5/ROSC_3") (pintype "bidirectional"))
    )
    (net (code "22") (name "/HEAT1") (class "Default")
      (node (ref "JP4") (pin "12") (pinfunction "12_12") (pintype "passive"))
      (node (ref "U1") (pin "5") (pinfunction "D_2_5") (pintype "passive"))
      (node (ref "U1") (pin "6") (pinfunction "D_3_6") (pintype "passive"))
      (node (ref "U1") (pin "7") (pinfunction "D_4_7") (pintype "passive"))
      (node (ref "U1") (pin "8") (pinfunction "D_8") (pintype "passive"))
    )
    (net (code "23") (name "/HEAT2") (class "Default")
      (node (ref "JP4") (pin "14") (pinfunction "14_14") (pintype "passive"))
      (node (ref "U2") (pin "5") (pinfunction "D_2_5") (pintype "passive"))
      (node (ref "U2") (pin "6") (pinfunction "D_3_6") (pintype "passive"))
      (node (ref "U2") (pin "7") (pinfunction "D_4_7") (pintype "passive"))
      (node (ref "U2") (pin "8") (pinfunction "D_8") (pintype "passive"))
    )
    (net (code "24") (name "/HEAT3") (class "Default")
      (node (ref "JP4") (pin "16") (pinfunction "16_16") (pintype "passive"))
      (node (ref "U3") (pin "5") (pinfunction "D_2_5") (pintype "passive"))
      (node (ref "U3") (pin "6") (pinfunction "D_3_6") (pintype "passive"))
      (node (ref "U3") (pin "7") (pinfunction "D_4_7") (pintype "passive"))
      (node (ref "U3") (pin "8") (pinfunction "D_8") (pintype "passive"))
    )
    (net (code "25") (name "/I2C_SCL") (class "Default")
      (node (ref "JP3") (pin "2") (pinfunction "2_2") (pintype "passive"))
      (node (ref "U4") (pin "13") (pinfunction "P3.2/UCB0SOMI/UCB0SCL_13") (pintype "bidirectional"))
    )
    (net (code "26") (name "/I2C_SDA") (class "Default")
      (node (ref "JP3") (pin "1") (pinfunction "1_1") (pintype "passive"))
      (node (ref "U4") (pin "12") (pinfunction "P3.1/UCB0SIMO/UCB0SDA_12") (pintype "bidirectional"))
    )
    (net (code "27") (name "/I_IN") (class "Default")
      (node (ref "C8") (pin "2") (pinfunction "2_2") (pintype "passive"))
      (node (ref "R25") (pin "1") (pinfunction "1_1") (pintype "passive"))
      (node (ref "U4") (pin "9") (pinfunction "P2.1/TAINCLK/SMCLK/A1_9") (pintype "bidirectional"))
    )
    (net (code "28") (name "/I_OUT") (class "Default")
      (node (ref "C9") (pin "2") (pinfunction "2_2") (pintype "passive"))
      (node (ref "R26") (pin "1") (pinfunction "1_1") (pintype "passive"))
      (node (ref "U4") (pin "8") (pinfunction "P2.0/ACLK/A0_8") (pintype "bidirectional"))
    )
    (net (code "29") (name "/LED_GND") (class "Default")
      (node (ref "J1") (pin "2") (pinfunction "2_2") (pintype "passive"))
      (node (ref "R11") (pin "1") (pinfunction "1_1") (pintype "passive"))
      (node (ref "R12") (pin "1") (pinfunction "1_1") (pintype "passive"))
    )
    (net (code "30") (name "/SC+") (class "Default")
      (node (ref "C32") (pin "2") (pinfunction "2_2") (pintype "passive"))
      (node (ref "JP5") (pin "2") (pinfunction "2_2") (pintype "passive"))
      (node (ref "R101") (pin "2") (pinfunction "2_2") (pintype "passive"))
      (node (ref "R102") (pin "2") (pinfunction "2_2") (pintype "passive"))
      (node (ref "R22") (pin "2") (pinfunction "2_2") (pintype "passive"))
      (node (ref "R29") (pin "2") (pinfunction "2_2") (pintype "passive"))
      (node (ref "R31") (pin "2") (pinfunction "2_2") (pintype "passive"))
      (node (ref "R40") (pin "1") (pinfunction "1_1") (pintype "passive"))
      (node (ref "R41") (pin "2") (pinfunction "2_2") (pintype "passive"))
      (node (ref "U10") (pin "5") (pinfunction "D_2_5") (pintype "passive"))
      (node (ref "U10") (pin "6") (pinfunction "D_3_6") (pintype "passive"))
      (node (ref "U10") (pin "7") (pinfunction "D_4_7") (pintype "passive"))
      (node (ref "U10") (pin "8") (pinfunction "D_8") (pintype "passive"))
    )
    (net (code "31") (name "/SC_OUT") (class "Default")
      (node (ref "C26") (pin "1") (pinfunction "1_1") (pintype "passive"))
      (node (ref "C37") (pin "1") (pinfunction "1_1") (pintype "passive"))
      (node (ref "C38") (pin "1") (pinfunction "1_1") (pintype "passive"))
      (node (ref "R32") (pin "2") (pinfunction "2_2") (pintype "passive"))
      (node (ref "R34") (pin "2") (pinfunction "2_2") (pintype "passive"))
      (node (ref "RSENSE1") (pin "I1") (pinfunction "I1_I1") (pintype "bidirectional"))
      (node (ref "R_SENSE1") (pin "I2") (pinfunction "I2_I2") (pintype "bidirectional"))
    )
    (net (code "32") (name "/V_BAT") (class "Default")
      (node (ref "C1") (pin "2") (pinfunction "2_2") (pintype "passive"))
      (node (ref "R1") (pin "1") (pinfunction "1_1") (pintype "passive"))
      (node (ref "U4") (pin "29") (pinfunction "P2.3/TA1/A3/VREF-/VEREF-_29") (pintype "bidirectional"))
    )
    (net (code "33") (name "/V_SC") (class "Default")
      (node (ref "C2") (pin "2") (pinfunction "2_2") (pintype "passive"))
      (node (ref "R2") (pin "1") (pinfunction "1_1") (pintype "passive"))
      (node (ref "U4") (pin "10") (pinfunction "P2.2/TA0/A2_10") (pintype "bidirectional"))
    )
    (net (code "34") (name "GND") (class "Default")
      (node (ref "C1") (pin "1") (pinfunction "1_1") (pintype "passive"))
      (node (ref "C10") (pin "2") (pinfunction "2_2") (pintype "passive"))
      (node (ref "C101") (pin "2") (pinfunction "2_2") (pintype "passive"))
      (node (ref "C102") (pin "2") (pinfunction "2_2") (pintype "passive"))
      (node (ref "C103") (pin "2") (pinfunction "2_2") (pintype "passive"))
      (node (ref "C104") (pin "2") (pinfunction "2_2") (pintype "passive"))
      (node (ref "C11") (pin "2") (pinfunction "2_2") (pintype "passive"))
      (node (ref "C12") (pin "2") (pinfunction "2_2") (pintype "passive"))
      (node (ref "C13") (pin "2") (pinfunction "2_2") (pintype "passive"))
      (node (ref "C14") (pin "2") (pinfunction "2_2") (pintype "passive"))
      (node (ref "C16") (pin "2") (pinfunction "2_2") (pintype "passive"))
      (node (ref "C17") (pin "2") (pinfunction "2_2") (pintype "passive"))
      (node (ref "C18") (pin "2") (pinfunction "2_2") (pintype "passive"))
      (node (ref "C19") (pin "2") (pinfunction "2_2") (pintype "passive"))
      (node (ref "C2") (pin "1") (pinfunction "1_1") (pintype "passive"))
      (node (ref "C20") (pin "2") (pinfunction "2_2") (pintype "passive"))
      (node (ref "C21") (pin "2") (pinfunction "2_2") (pintype "passive"))
      (node (ref "C22") (pin "2") (pinfunction "2_2") (pintype "passive"))
      (node (ref "C23") (pin "2") (pinfunction "2_2") (pintype "passive"))
      (node (ref "C24") (pin "2") (pinfunction "2_2") (pintype "passive"))
      (node (ref "C25") (pin "2") (pinfunction "2_2") (pintype "passive"))
      (node (ref "C27") (pin "1") (pinfunction "1_1") (pintype "passive"))
      (node (ref "C28") (pin "1") (pinfunction "1_1") (pintype "passive"))
      (node (ref "C29") (pin "1") (pinfunction "1_1") (pintype "passive"))
      (node (ref "C3") (pin "2") (pinfunction "2_2") (pintype "passive"))
      (node (ref "C30") (pin "1") (pinfunction "1_1") (pintype "passive"))
      (node (ref "C32") (pin "1") (pinfunction "1_1") (pintype "passive"))
      (node (ref "C33") (pin "2") (pinfunction "2_2") (pintype "passive"))
      (node (ref "C34") (pin "2") (pinfunction "2_2") (pintype "passive"))
      (node (ref "C35") (pin "2") (pinfunction "2_2") (pintype "passive"))
      (node (ref "C36") (pin "2") (pinfunction "2_2") (pintype "passive"))
      (node (ref "C37") (pin "2") (pinfunction "2_2") (pintype "passive"))
      (node (ref "C38") (pin "2") (pinfunction "2_2") (pintype "passive"))
      (node (ref "C4") (pin "2") (pinfunction "2_2") (pintype "passive"))
      (node (ref "C5") (pin "2") (pinfunction "2_2") (pintype "passive"))
      (node (ref "C6") (pin "2") (pinfunction "2_2") (pintype "passive"))
      (node (ref "C7") (pin "-") (pinfunction "-_-") (pintype "passive"))
      (node (ref "C8") (pin "1") (pinfunction "1_1") (pintype "passive"))
      (node (ref "C9") (pin "1") (pinfunction "1_1") (pintype "passive"))
      (node (ref "C_IC1") (pin "1") (pinfunction "1_1") (pintype "passive"))
      (node (ref "IC1") (pin "4") (pinfunction "V-_4") (pintype "power_in"))
      (node (ref "J1") (pin "1") (pinfunction "1_1") (pintype "passive"))
      (node (ref "J4") (pin "1") (pinfunction "1_1") (pintype "passive"))
      (node (ref "J5") (pin "1") (pinfunction "1_1") (pintype "passive"))
      (node (ref "J6") (pin "1") (pinfunction "1_1") (pintype "passive"))
      (node (ref "JP1") (pin "2") (pinfunction "2_2") (pintype "passive"))
      (node (ref "JP1") (pin "4") (pinfunction "4_4") (pintype "passive"))
      (node (ref "JP1") (pin "6") (pinfunction "6_6") (pintype "passive"))
      (node (ref "JP1") (pin "8") (pinfunction "8_8") (pintype "passive"))
      (node (ref "JP4") (pin "1") (pinfunction "1_1") (pintype "passive"))
      (node (ref "JP4") (pin "3") (pinfunction "3_3") (pintype "passive"))
      (node (ref "JP4") (pin "5") (pinfunction "5_5") (pintype "passive"))
      (node (ref "JP4") (pin "7") (pinfunction "7_7") (pintype "passive"))
      (node (ref "JP4") (pin "9") (pinfunction "9_9") (pintype "passive"))
      (node (ref "JP5") (pin "1") (pinfunction "1_1") (pintype "passive"))
      (node (ref "JP6") (pin "1") (pinfunction "1_1") (pintype "passive"))
      (node (ref "Q1") (pin "P3") (pinfunction "GND_P3") (pintype "power_in"))
      (node (ref "Q100") (pin "2") (pinfunction "S_2") (pintype "passive"))
      (node (ref "R10") (pin "2") (pinfunction "2_2") (pintype "passive"))
      (node (ref "R100") (pin "1") (pinfunction "1_1") (pintype "passive"))
      (node (ref "R103") (pin "1") (pinfunction "1_1") (pintype "passive"))
      (node (ref "R104") (pin "2") (pinfunction "2_2") (pintype "passive"))
      (node (ref "R18") (pin "2") (pinfunction "2_2") (pintype "passive"))
      (node (ref "R20") (pin "1") (pinfunction "1_1") (pintype "passive"))
      (node (ref "R21") (pin "1") (pinfunction "1_1") (pintype "passive"))
      (node (ref "R27") (pin "2") (pinfunction "2_2") (pintype "passive"))
      (node (ref "R30") (pin "1") (pinfunction "1_1") (pintype "passive"))
      (node (ref "R33") (pin "1") (pinfunction "1_1") (pintype "passive"))
      (node (ref "R35") (pin "1") (pinfunction "1_1") (pintype "passive"))
      (node (ref "R36") (pin "1") (pinfunction "1_1") (pintype "passive"))
      (node (ref "R4") (pin "2") (pinfunction "2_2") (pintype "passive"))
      (node (ref "R6") (pin "2") (pinfunction "2_2") (pintype "passive"))
      (node (ref "R8") (pin "2") (pinfunction "2_2") (pintype "passive"))
      (node (ref "U$1") (pin "P$20") (pinfunction "AGND_P$20") (pintype "bidirectional"))
      (node (ref "U$1") (pin "PGND1") (pinfunction "PGND_PGND1") (pintype "bidirectional"))
      (node (ref "U$1") (pin "PGND10") (pinfunction "PGND_PGND10") (pintype "bidirectional"))
      (node (ref "U$1") (pin "PGND11") (pinfunction "PGND_PGND11") (pintype "bidirectional"))
      (node (ref "U$1") (pin "PGND12") (pinfunction "PGND_PGND12") (pintype "bidirectional"))
      (node (ref "U$1") (pin "PGND2") (pinfunction "PGND_PGND2") (pintype "bidirectional"))
      (node (ref "U$1") (pin "PGND3") (pinfunction "PGND_PGND3") (pintype "bidirectional"))
      (node (ref "U$1") (pin "PGND4") (pinfunction "PGND_PGND4") (pintype "bidirectional"))
      (node (ref "U$1") (pin "PGND5") (pinfunction "PGND_PGND5") (pintype "bidirectional"))
      (node (ref "U$1") (pin "PGND6") (pinfunction "PGND_PGND6") (pintype "bidirectional"))
      (node (ref "U$1") (pin "PGND7") (pinfunction "PGND_PGND7") (pintype "bidirectional"))
      (node (ref "U$1") (pin "PGND8") (pinfunction "PGND_PGND8") (pintype "bidirectional"))
      (node (ref "U$1") (pin "PGND9") (pinfunction "PGND_PGND9") (pintype "bidirectional"))
      (node (ref "U$2") (pin "1") (pinfunction "REF_1") (pintype "bidirectional"))
      (node (ref "U$2") (pin "2") (pinfunction "GND_2") (pintype "bidirectional"))
      (node (ref "U$3") (pin "1") (pinfunction "REF_1") (pintype "bidirectional"))
      (node (ref "U$3") (pin "2") (pinfunction "GND_2") (pintype "bidirectional"))
      (node (ref "U1") (pin "1") (pinfunction "S_2_1") (pintype "passive"))
      (node (ref "U1") (pin "2") (pinfunction "S_3_2") (pintype "passive"))
      (node (ref "U1") (pin "3") (pinfunction "S_3") (pintype "passive"))
      (node (ref "U100") (pin "10") (pinfunction "PFM_PWM_10") (pintype "input"))
      (node (ref "U100") (pin "2") (pinfunction "PGND_2") (pintype "power_in"))
      (node (ref "U100") (pin "9") (pinfunction "GND_9") (pintype "power_in"))
      (node (ref "U11") (pin "1") (pinfunction "S_2_1") (pintype "passive"))
      (node (ref "U11") (pin "2") (pinfunction "S_3_2") (pintype "passive"))
      (node (ref "U11") (pin "3") (pinfunction "S_3") (pintype "passive"))
      (node (ref "U2") (pin "1") (pinfunction "S_2_1") (pintype "passive"))
      (node (ref "U2") (pin "2") (pinfunction "S_3_2") (pintype "passive"))
      (node (ref "U2") (pin "3") (pinfunction "S_3") (pintype "passive"))
      (node (ref "U3") (pin "1") (pinfunction "S_2_1") (pintype "passive"))
      (node (ref "U3") (pin "2") (pinfunction "S_3_2") (pintype "passive"))
      (node (ref "U3") (pin "3") (pinfunction "S_3") (pintype "passive"))
      (node (ref "U4") (pin "15") (pinfunction "AVSS_15") (pintype "bidirectional"))
      (node (ref "U4") (pin "4") (pinfunction "DVSS_4") (pintype "bidirectional"))
      (node (ref "U5") (pin "1") (pinfunction "GND_1") (pintype "bidirectional"))
      (node (ref "U6") (pin "10") (pinfunction "PFM_PWM_10") (pintype "input"))
      (node (ref "U6") (pin "2") (pinfunction "PGND_2") (pintype "power_in"))
      (node (ref "U6") (pin "9") (pinfunction "GND_9") (pintype "power_in"))
      (node (ref "U7") (pin "10") (pinfunction "PFM_PWM_10") (pintype "input"))
      (node (ref "U7") (pin "2") (pinfunction "PGND_2") (pintype "power_in"))
      (node (ref "U7") (pin "9") (pinfunction "GND_9") (pintype "power_in"))
      (node (ref "U8") (pin "EXPAD") (pinfunction "GND_EXPAD") (pintype "power_in"))
      (node (ref "U8") (pin "GND1") (pinfunction "GND1_GND1") (pintype "power_in"))
      (node (ref "U8") (pin "GND2") (pinfunction "GND2_GND2") (pintype "power_in"))
      (node (ref "U8") (pin "GND3") (pinfunction "GND3_GND3") (pintype "power_in"))
      (node (ref "U8") (pin "GND4") (pinfunction "GND4_GND4") (pintype "power_in"))
      (node (ref "U8") (pin "GND5") (pinfunction "GND5_GND5") (pintype "power_in"))
      (node (ref "U9") (pin "11") (pinfunction "GND_11") (pintype "power_in"))
      (node (ref "U9") (pin "17") (pinfunction "EPAD_17") (pintype "power_in"))
      (node (ref "U9") (pin "7") (pinfunction "TERM_EN_7") (pintype "input"))
      (node (ref "U9") (pin "V") (pinfunction "EPAD_V") (pintype "power_in"))
      (node (ref "U9") (pin "V_1") (pinfunction "EPAD_V_1") (pintype "power_in"))
      (node (ref "U9") (pin "V_2") (pinfunction "EPAD_V_2") (pintype "power_in"))
      (node (ref "U9") (pin "V_3") (pinfunction "EPAD_V_3") (pintype "power_in"))
    )
    (net (code "35") (name "Net-(+3V3_1-PadC)") (class "Default")
      (node (ref "+3V3_1") (pin "C") (pinfunction "C_C") (pintype "passive"))
      (node (ref "R13") (pin "2") (pinfunction "2_2") (pintype "passive"))
    )
    (net (code "36") (name "Net-(+3V3_2-PadC)") (class "Default")
      (node (ref "+3V3_2") (pin "C") (pinfunction "C_C") (pintype "passive"))
      (node (ref "R14") (pin "2") (pinfunction "2_2") (pintype "passive"))
    )
    (net (code "37") (name "Net-(+3V3_M-PadC)") (class "Default")
      (node (ref "+3V3_M") (pin "C") (pinfunction "C_C") (pintype "passive"))
      (node (ref "R12") (pin "2") (pinfunction "2_2") (pintype "passive"))
    )
    (net (code "38") (name "Net-(+5V-PadC)") (class "Default")
      (node (ref "+5V") (pin "C") (pinfunction "C_C") (pintype "passive"))
      (node (ref "R15") (pin "2") (pinfunction "2_2") (pintype "passive"))
    )
    (net (code "39") (name "Net-(+11V-PadC)") (class "Default")
      (node (ref "+11V") (pin "C") (pinfunction "C_C") (pintype "passive"))
      (node (ref "R16") (pin "2") (pinfunction "2_2") (pintype "passive"))
    )
    (net (code "40") (name "Net-(6.8UH-Pad2)") (class "Default")
      (node (ref "6.8UH") (pin "2") (pinfunction "2_2") (pintype "passive"))
      (node (ref "R_SENSE1") (pin "I1") (pinfunction "I1_I1") (pintype "bidirectional"))
    )
    (net (code "41") (name "Net-(C22-Pad1)") (class "Default")
      (node (ref "C22") (pin "1") (pinfunction "1_1") (pintype "passive"))
      (node (ref "R41") (pin "1") (pinfunction "1_1") (pintype "passive"))
    )
    (net (code "42") (name "Net-(C25-Pad1)") (class "Default")
      (node (ref "C25") (pin "1") (pinfunction "1_1") (pintype "passive"))
      (node (ref "R37") (pin "1") (pinfunction "1_1") (pintype "passive"))
    )
    (net (code "43") (name "Net-(D1-A1)") (class "Default")
      (node (ref "C101") (pin "1") (pinfunction "1_1") (pintype "passive"))
      (node (ref "D1") (pin "1") (pinfunction "A1_1") (pintype "passive"))
      (node (ref "D1") (pin "2") (pinfunction "A2_2") (pintype "passive"))
      (node (ref "U9") (pin "12") (pinfunction "REGN_12") (pintype "power_in"))
    )
    (net (code "44") (name "Net-(D1-CC)") (class "Default")
      (node (ref "C100") (pin "2") (pinfunction "2_2") (pintype "passive"))
      (node (ref "D1") (pin "3") (pinfunction "CC_3") (pintype "passive"))
      (node (ref "U9") (pin "16") (pinfunction "BTST_16") (pintype "power_in"))
    )
    (net (code "45") (name "Net-(IC1A-+IN)") (class "Default")
      (node (ref "IC1") (pin "3") (pinfunction "+IN_3") (pintype "input"))
      (node (ref "R21") (pin "2") (pinfunction "2_2") (pintype "passive"))
      (node (ref "R23") (pin "1") (pinfunction "1_1") (pintype "passive"))
    )
    (net (code "46") (name "Net-(IC1A--IN)") (class "Default")
      (node (ref "IC1") (pin "2") (pinfunction "-IN_2") (pintype "input"))
      (node (ref "R10") (pin "1") (pinfunction "1_1") (pintype "passive"))
      (node (ref "R9") (pin "2") (pinfunction "2_2") (pintype "passive"))
    )
    (net (code "47") (name "Net-(IC1A-OUT)") (class "Default")
      (node (ref "IC1") (pin "1") (pinfunction "OUT_1") (pintype "output"))
      (node (ref "R1") (pin "2") (pinfunction "2_2") (pintype "passive"))
      (node (ref "R9") (pin "1") (pinfunction "1_1") (pintype "passive"))
    )
    (net (code "48") (name "Net-(IC1B-+IN)") (class "Default")
      (node (ref "IC1") (pin "5") (pinfunction "+IN_5") (pintype "input"))
      (node (ref "R20") (pin "2") (pinfunction "2_2") (pintype "passive"))
      (node (ref "R22") (pin "1") (pinfunction "1_1") (pintype "passive"))
    )
    (net (code "49") (name "Net-(IC1B--IN)") (class "Default")
      (node (ref "IC1") (pin "6") (pinfunction "-IN_6") (pintype "input"))
      (node (ref "R17") (pin "2") (pinfunction "2_2") (pintype "passive"))
      (node (ref "R18") (pin "1") (pinfunction "1_1") (pintype "passive"))
    )
    (net (code "50") (name "Net-(IC1B-OUT)") (class "Default")
      (node (ref "IC1") (pin "7") (pinfunction "OUT_7") (pintype "output"))
      (node (ref "R17") (pin "1") (pinfunction "1_1") (pintype "passive"))
      (node (ref "R2") (pin "2") (pinfunction "2_2") (pintype "passive"))
    )
    (net (code "51") (name "Net-(J4-Pad2)") (class "Default")
      (node (ref "J4") (pin "2") (pinfunction "2_2") (pintype "passive"))
      (node (ref "R14") (pin "1") (pinfunction "1_1") (pintype "passive"))
    )
    (net (code "52") (name "Net-(J5-Pad2)") (class "Default")
      (node (ref "J5") (pin "2") (pinfunction "2_2") (pintype "passive"))
      (node (ref "R15") (pin "1") (pinfunction "1_1") (pintype "passive"))
    )
    (net (code "53") (name "Net-(J6-Pad2)") (class "Default")
      (node (ref "J6") (pin "2") (pinfunction "2_2") (pintype "passive"))
      (node (ref "R16") (pin "1") (pinfunction "1_1") (pintype "passive"))
    )
    (net (code "54") (name "Net-(J7-Pad2)") (class "Default")
      (node (ref "J7") (pin "2") (pinfunction "2_2") (pintype "passive"))
      (node (ref "STAT2") (pin "C") (pinfunction "C_C") (pintype "passive"))
    )
    (net (code "55") (name "Net-(J8-Pad2)") (class "Default")
      (node (ref "J8") (pin "2") (pinfunction "2_2") (pintype "passive"))
      (node (ref "STAT1") (pin "C") (pinfunction "C_C") (pintype "passive"))
    )
    (net (code "56") (name "Net-(L1-1)") (class "Default")
      (node (ref "L1") (pin "P$1") (pinfunction "1_P$1") (pintype "passive"))
      (node (ref "U6") (pin "3") (pinfunction "L1_3") (pintype "passive"))
    )
    (net (code "57") (name "Net-(L1-2)") (class "Default")
      (node (ref "L1") (pin "P$2") (pinfunction "2_P$2") (pintype "passive"))
      (node (ref "U6") (pin "1") (pinfunction "L2_1") (pintype "passive"))
    )
    (net (code "58") (name "Net-(L2-1)") (class "Default")
      (node (ref "L2") (pin "P$1") (pinfunction "1_P$1") (pintype "passive"))
      (node (ref "U7") (pin "3") (pinfunction "L1_3") (pintype "passive"))
    )
    (net (code "59") (name "Net-(L2-2)") (class "Default")
      (node (ref "L2") (pin "P$2") (pinfunction "2_P$2") (pintype "passive"))
      (node (ref "U7") (pin "1") (pinfunction "L2_1") (pintype "passive"))
    )
    (net (code "60") (name "Net-(L3-2)") (class "Default")
      (node (ref "L3") (pin "P$2") (pinfunction "2_P$2") (pintype "passive"))
      (node (ref "U8") (pin "1") (pinfunction "SW_1") (pintype "power_in"))
      (node (ref "U8") (pin "2") (pinfunction "SW_2") (pintype "power_in"))
    )
    (net (code "61") (name "Net-(L4-2)") (class "Default")
      (node (ref "C31") (pin "1") (pinfunction "1_1") (pintype "passive"))
      (node (ref "L4") (pin "P$2") (pinfunction "2_P$2") (pintype "passive"))
      (node (ref "R39") (pin "2") (pinfunction "2_2") (pintype "passive"))
      (node (ref "U$1") (pin "P$4") (pinfunction "SW1_P$4") (pintype "bidirectional"))
      (node (ref "U$1") (pin "P$5") (pinfunction "SW2_P$5") (pintype "bidirectional"))
      (node (ref "U$1") (pin "P$6") (pinfunction "SW3_P$6") (pintype "bidirectional"))
      (node (ref "U$1") (pin "P$7") (pinfunction "SW4_P$7") (pintype "bidirectional"))
    )
    (net (code "62") (name "Net-(L100-1)") (class "Default")
      (node (ref "L100") (pin "P$1") (pinfunction "1_P$1") (pintype "passive"))
      (node (ref "U100") (pin "3") (pinfunction "L1_3") (pintype "passive"))
    )
    (net (code "63") (name "Net-(L100-2)") (class "Default")
      (node (ref "L100") (pin "P$2") (pinfunction "2_P$2") (pintype "passive"))
      (node (ref "U100") (pin "1") (pinfunction "L2_1") (pintype "passive"))
    )
    (net (code "64") (name "Net-(Q1-1)") (class "Default")
      (node (ref "Q1") (pin "P1") (pinfunction "1_P1") (pintype "bidirectional"))
      (node (ref "U4") (pin "6") (pinfunction "XIN/P2.6_6") (pintype "bidirectional"))
    )
    (net (code "65") (name "Net-(Q1-2)") (class "Default")
      (node (ref "Q1") (pin "P2") (pinfunction "2_P2") (pintype "bidirectional"))
      (node (ref "U4") (pin "5") (pinfunction "XOUT/P2.7_5") (pintype "bidirectional"))
    )
    (net (code "66") (name "Net-(Q100-D)") (class "Default")
      (node (ref "Q100") (pin "3") (pinfunction "D_3") (pintype "passive"))
      (node (ref "R100") (pin "2") (pinfunction "2_2") (pintype "passive"))
      (node (ref "R101") (pin "1") (pinfunction "1_1") (pintype "passive"))
      (node (ref "U9") (pin "2") (pinfunction "MPPSET_2") (pintype "input"))
    )
    (net (code "67") (name "Net-(R11-Pad2)") (class "Default")
      (node (ref "R11") (pin "2") (pinfunction "2_2") (pintype "passive"))
      (node (ref "VCC") (pin "C") (pinfunction "C_C") (pintype "passive"))
    )
    (net (code "68") (name "Net-(R29-Pad1)") (class "Default")
      (node (ref "R29") (pin "1") (pinfunction "1_1") (pintype "passive"))
      (node (ref "STAT2") (pin "A") (pinfunction "A_A") (pintype "passive"))
    )
    (net (code "69") (name "Net-(R31-Pad1)") (class "Default")
      (node (ref "R31") (pin "1") (pinfunction "1_1") (pintype "passive"))
      (node (ref "STAT1") (pin "A") (pinfunction "A_A") (pintype "passive"))
    )
    (net (code "70") (name "Net-(U$1-BOOT)") (class "Default")
      (node (ref "C31") (pin "2") (pinfunction "2_2") (pintype "passive"))
      (node (ref "U$1") (pin "P$8") (pinfunction "BOOT_P$8") (pintype "bidirectional"))
    )
    (net (code "71") (name "Net-(U$1-COMP)") (class "Default")
      (node (ref "C24") (pin "1") (pinfunction "1_1") (pintype "passive"))
      (node (ref "R37") (pin "2") (pinfunction "2_2") (pintype "passive"))
      (node (ref "U$1") (pin "P$18") (pinfunction "COMP_P$18") (pintype "bidirectional"))
    )
    (net (code "72") (name "Net-(U$1-FB)") (class "Default")
      (node (ref "R36") (pin "2") (pinfunction "2_2") (pintype "passive"))
      (node (ref "R38") (pin "1") (pinfunction "1_1") (pintype "passive"))
      (node (ref "U$1") (pin "P$17") (pinfunction "FB_P$17") (pintype "bidirectional"))
    )
    (net (code "73") (name "Net-(U$1-FSW)") (class "Default")
      (node (ref "R39") (pin "1") (pinfunction "1_1") (pintype "passive"))
      (node (ref "U$1") (pin "P$3") (pinfunction "FSW_P$3") (pintype "bidirectional"))
    )
    (net (code "74") (name "Net-(U$1-ILIM)") (class "Default")
      (node (ref "R35") (pin "2") (pinfunction "2_2") (pintype "passive"))
      (node (ref "U$1") (pin "P$19") (pinfunction "ILIM_P$19") (pintype "bidirectional"))
    )
    (net (code "75") (name "Net-(U$1-SS)") (class "Default")
      (node (ref "C36") (pin "1") (pinfunction "1_1") (pintype "passive"))
      (node (ref "U$1") (pin "P$10") (pinfunction "SS_P$10") (pintype "bidirectional"))
    )
    (net (code "76") (name "Net-(U$1-VCC)") (class "Default")
      (node (ref "C23") (pin "1") (pinfunction "1_1") (pintype "passive"))
      (node (ref "U$1") (pin "P$1") (pinfunction "VCC_P$1") (pintype "bidirectional"))
    )
    (net (code "77") (name "Net-(U$2-IN+)") (class "Default")
      (node (ref "RSENSE1") (pin "V1") (pinfunction "V1_V1") (pintype "bidirectional"))
      (node (ref "U$2") (pin "4") (pinfunction "IN+_4") (pintype "bidirectional"))
    )
    (net (code "78") (name "Net-(U$2-IN-)") (class "Default")
      (node (ref "RSENSE1") (pin "V2") (pinfunction "V2_V2") (pintype "bidirectional"))
      (node (ref "U$2") (pin "5") (pinfunction "IN-_5") (pintype "bidirectional"))
    )
    (net (code "79") (name "Net-(U$2-OUT)") (class "Default")
      (node (ref "R25") (pin "2") (pinfunction "2_2") (pintype "passive"))
      (node (ref "U$2") (pin "6") (pinfunction "OUT_6") (pintype "bidirectional"))
    )
    (net (code "80") (name "Net-(U$3-IN+)") (class "Default")
      (node (ref "R_SENSE2") (pin "V1") (pinfunction "V1_V1") (pintype "bidirectional"))
      (node (ref "U$3") (pin "4") (pinfunction "IN+_4") (pintype "bidirectional"))
    )
    (net (code "81") (name "Net-(U$3-IN-)") (class "Default")
      (node (ref "R_SENSE2") (pin "V2") (pinfunction "V2_V2") (pintype "bidirectional"))
      (node (ref "U$3") (pin "5") (pinfunction "IN-_5") (pintype "bidirectional"))
    )
    (net (code "82") (name "Net-(U$3-OUT)") (class "Default")
      (node (ref "R26") (pin "2") (pinfunction "2_2") (pintype "passive"))
      (node (ref "U$3") (pin "6") (pinfunction "OUT_6") (pintype "bidirectional"))
    )
    (net (code "83") (name "Net-(U1-G)") (class "Default")
      (node (ref "R3") (pin "1") (pinfunction "1_1") (pintype "passive"))
      (node (ref "U1") (pin "4") (pinfunction "G_4") (pintype "passive"))
    )
    (net (code "84") (name "Net-(U2-G)") (class "Default")
      (node (ref "R5") (pin "1") (pinfunction "1_1") (pintype "passive"))
      (node (ref "U2") (pin "4") (pinfunction "G_4") (pintype "passive"))
    )
    (net (code "85") (name "Net-(U3-G)") (class "Default")
      (node (ref "R7") (pin "1") (pinfunction "1_1") (pintype "passive"))
      (node (ref "U3") (pin "4") (pinfunction "G_4") (pintype "passive"))
    )
    (net (code "86") (name "Net-(U4-AVCC)") (class "Default")
      (node (ref "C3") (pin "1") (pinfunction "1_1") (pintype "passive"))
      (node (ref "FERRITE") (pin "2") (pinfunction "2_2") (pintype "passive"))
      (node (ref "U4") (pin "16") (pinfunction "AVCC_16") (pintype "bidirectional"))
    )
    (net (code "87") (name "Net-(U4-RST{slash}NMI{slash}SBWTDIO)") (class "Default")
      (node (ref "JP2") (pin "1") (pinfunction "1_1") (pintype "passive"))
      (node (ref "R19") (pin "1") (pinfunction "1_1") (pintype "passive"))
      (node (ref "U4") (pin "7") (pinfunction "RST/NMI/SBWTDIO_7") (pintype "bidirectional"))
    )
    (net (code "88") (name "Net-(U4-TEST{slash}SBWTCK)") (class "Default")
      (node (ref "JP2") (pin "2") (pinfunction "2_2") (pintype "passive"))
      (node (ref "U4") (pin "1") (pinfunction "TEST/SBWTCK_1") (pintype "bidirectional"))
    )
    (net (code "89") (name "Net-(U8-PG)") (class "Default")
      (node (ref "R28") (pin "1") (pinfunction "1_1") (pintype "passive"))
      (node (ref "U8") (pin "5") (pinfunction "PG_5") (pintype "output"))
    )
    (net (code "90") (name "Net-(U8-SS)") (class "Default")
      (node (ref "C13") (pin "1") (pinfunction "1_1") (pintype "passive"))
      (node (ref "U8") (pin "6") (pinfunction "SS_6") (pintype "bidirectional"))
    )
    (net (code "91") (name "Net-(U9-SRN)") (class "Default")
      (node (ref "C15") (pin "1") (pinfunction "1_1") (pintype "passive"))
      (node (ref "R_SENSE1") (pin "V2") (pinfunction "V2_V2") (pintype "bidirectional"))
      (node (ref "U9") (pin "9") (pinfunction "SRN_9") (pintype "input"))
    )
    (net (code "92") (name "Net-(U9-SRP)") (class "Default")
      (node (ref "C15") (pin "2") (pinfunction "2_2") (pintype "passive"))
      (node (ref "R_SENSE1") (pin "V1") (pinfunction "V1_V1") (pintype "bidirectional"))
      (node (ref "U9") (pin "10") (pinfunction "SRP_10") (pintype "bidirectional"))
    )
    (net (code "93") (name "Net-(U9-STAT1)") (class "Default")
      (node (ref "J8") (pin "1") (pinfunction "1_1") (pintype "passive"))
      (node (ref "U9") (pin "3") (pinfunction "STAT1_3") (pintype "output"))
    )
    (net (code "94") (name "Net-(U9-STAT2)") (class "Default")
      (node (ref "J7") (pin "1") (pinfunction "1_1") (pintype "passive"))
      (node (ref "U9") (pin "5") (pinfunction "STAT2_5") (pintype "output"))
    )
    (net (code "95") (name "Net-(U9-VCC)") (class "Default")
      (node (ref "C21") (pin "1") (pinfunction "1_1") (pintype "passive"))
      (node (ref "R40") (pin "2") (pinfunction "2_2") (pintype "passive"))
      (node (ref "U9") (pin "1") (pinfunction "VCC_1") (pintype "power_in"))
    )
    (net (code "96") (name "Net-(U9-VFB)") (class "Default")
      (node (ref "C26") (pin "2") (pinfunction "2_2") (pintype "passive"))
      (node (ref "R32") (pin "1") (pinfunction "1_1") (pintype "passive"))
      (node (ref "R33") (pin "2") (pinfunction "2_2") (pintype "passive"))
      (node (ref "R34") (pin "1") (pinfunction "1_1") (pintype "passive"))
      (node (ref "U9") (pin "8") (pinfunction "VFB_8") (pintype "input"))
    )
    (net (code "97") (name "Net-(U9-VREF)") (class "Default")
      (node (ref "C20") (pin "1") (pinfunction "1_1") (pintype "passive"))
      (node (ref "U9") (pin "6") (pinfunction "VREF_6") (pintype "power_in"))
    )
    (net (code "98") (name "Net-(U10-G)") (class "Default")
      (node (ref "U10") (pin "4") (pinfunction "G_4") (pintype "passive"))
      (node (ref "U9") (pin "15") (pinfunction "HIDRV_15") (pintype "output"))
    )
    (net (code "99") (name "Net-(U10-S)") (class "Default")
      (node (ref "6.8UH") (pin "1") (pinfunction "1_1") (pintype "passive"))
      (node (ref "C100") (pin "1") (pinfunction "1_1") (pintype "passive"))
      (node (ref "U10") (pin "1") (pinfunction "S_2_1") (pintype "passive"))
      (node (ref "U10") (pin "2") (pinfunction "S_3_2") (pintype "passive"))
      (node (ref "U10") (pin "3") (pinfunction "S_3") (pintype "passive"))
      (node (ref "U11") (pin "5") (pinfunction "D_2_5") (pintype "passive"))
      (node (ref "U11") (pin "6") (pinfunction "D_3_6") (pintype "passive"))
      (node (ref "U11") (pin "7") (pinfunction "D_4_7") (pintype "passive"))
      (node (ref "U11") (pin "8") (pinfunction "D_8") (pintype "passive"))
      (node (ref "U9") (pin "14") (pinfunction "PH_14") (pintype "power_in"))
    )
    (net (code "100") (name "Net-(U11-G)") (class "Default")
      (node (ref "U11") (pin "4") (pinfunction "G_4") (pintype "passive"))
      (node (ref "U9") (pin "13") (pinfunction "LODRV_13") (pintype "output"))
    )
    (net (code "101") (name "unconnected-(R13-Pad1)") (class "Default")
      (node (ref "R13") (pin "1") (pinfunction "1_1") (pintype "passive"))
    )
    (net (code "102") (name "unconnected-(U$1-MODE-PadP$13)") (class "Default")
      (node (ref "U$1") (pin "P$13") (pinfunction "MODE_P$13") (pintype "bidirectional"))
    )
    (net (code "103") (name "unconnected-(U4-P3.3{slash}UCB0CLK{slash}UCA0STE-Pad14)") (class "Default")
      (node (ref "U4") (pin "14") (pinfunction "P3.3/UCB0CLK/UCA0STE_14") (pintype "bidirectional"))
    )
    (net (code "104") (name "unconnected-(U4-P3.4{slash}UCA0TXD{slash}UCA0SIMO-Pad25)") (class "Default")
      (node (ref "U4") (pin "25") (pinfunction "P3.4/UCA0TXD/UCA0SIMO_25") (pintype "bidirectional"))
    )
    (net (code "105") (name "unconnected-(U4-P3.5{slash}UCA0RXD{slash}UCA0SOMI-Pad26)") (class "Default")
      (node (ref "U4") (pin "26") (pinfunction "P3.5/UCA0RXD/UCA0SOMI_26") (pintype "bidirectional"))
    )
    (net (code "106") (name "unconnected-(U4-P4.0{slash}TB0-Pad17)") (class "Default")
      (node (ref "U4") (pin "17") (pinfunction "P4.0/TB0_17") (pintype "bidirectional"))
    )
    (net (code "107") (name "unconnected-(U4-P4.1{slash}TB1-Pad18)") (class "Default")
      (node (ref "U4") (pin "18") (pinfunction "P4.1/TB1_18") (pintype "bidirectional"))
    )
    (net (code "108") (name "unconnected-(U4-P4.2{slash}TB2-Pad19)") (class "Default")
      (node (ref "U4") (pin "19") (pinfunction "P4.2/TB2_19") (pintype "bidirectional"))
    )
    (net (code "109") (name "unconnected-(U4-P4.3{slash}TB0{slash}A12-Pad20)") (class "Default")
      (node (ref "U4") (pin "20") (pinfunction "P4.3/TB0/A12_20") (pintype "bidirectional"))
    )
    (net (code "110") (name "unconnected-(U4-P4.4{slash}TB1{slash}A13-Pad21)") (class "Default")
      (node (ref "U4") (pin "21") (pinfunction "P4.4/TB1/A13_21") (pintype "bidirectional"))
    )
    (net (code "111") (name "unconnected-(U4-P4.5{slash}TB2{slash}A14-Pad22)") (class "Default")
      (node (ref "U4") (pin "22") (pinfunction "P4.5/TB2/A14_22") (pintype "bidirectional"))
    )
    (net (code "112") (name "unconnected-(U4-P4.6{slash}TBOUTH{slash}A15-Pad23)") (class "Default")
      (node (ref "U4") (pin "23") (pinfunction "P4.6/TBOUTH/A15_23") (pintype "bidirectional"))
    )
    (net (code "113") (name "unconnected-(U4-P4.7{slash}TBCLK-Pad24)") (class "Default")
      (node (ref "U4") (pin "24") (pinfunction "P4.7/TBCLK_24") (pintype "bidirectional"))
    )
    (net (code "114") (name "unconnected-(U5-OC-Pad5)") (class "Default")
      (node (ref "U5") (pin "5") (pinfunction "OC_5") (pintype "bidirectional"))
    )
    (net (code "115") (name "unconnected-(U8-HYS-Pad8)") (class "Default")
      (node (ref "U8") (pin "8") (pinfunction "HYS_8") (pintype "output"))
    )
    (net (code "116") (name "unconnected-(U9-TS-Pad4)") (class "Default")
      (node (ref "U9") (pin "4") (pinfunction "TS_4") (pintype "input"))
    )
  )
)
